# vm_mini_exp5.net
KiCad netlist of a schematic drawn in EAGLE
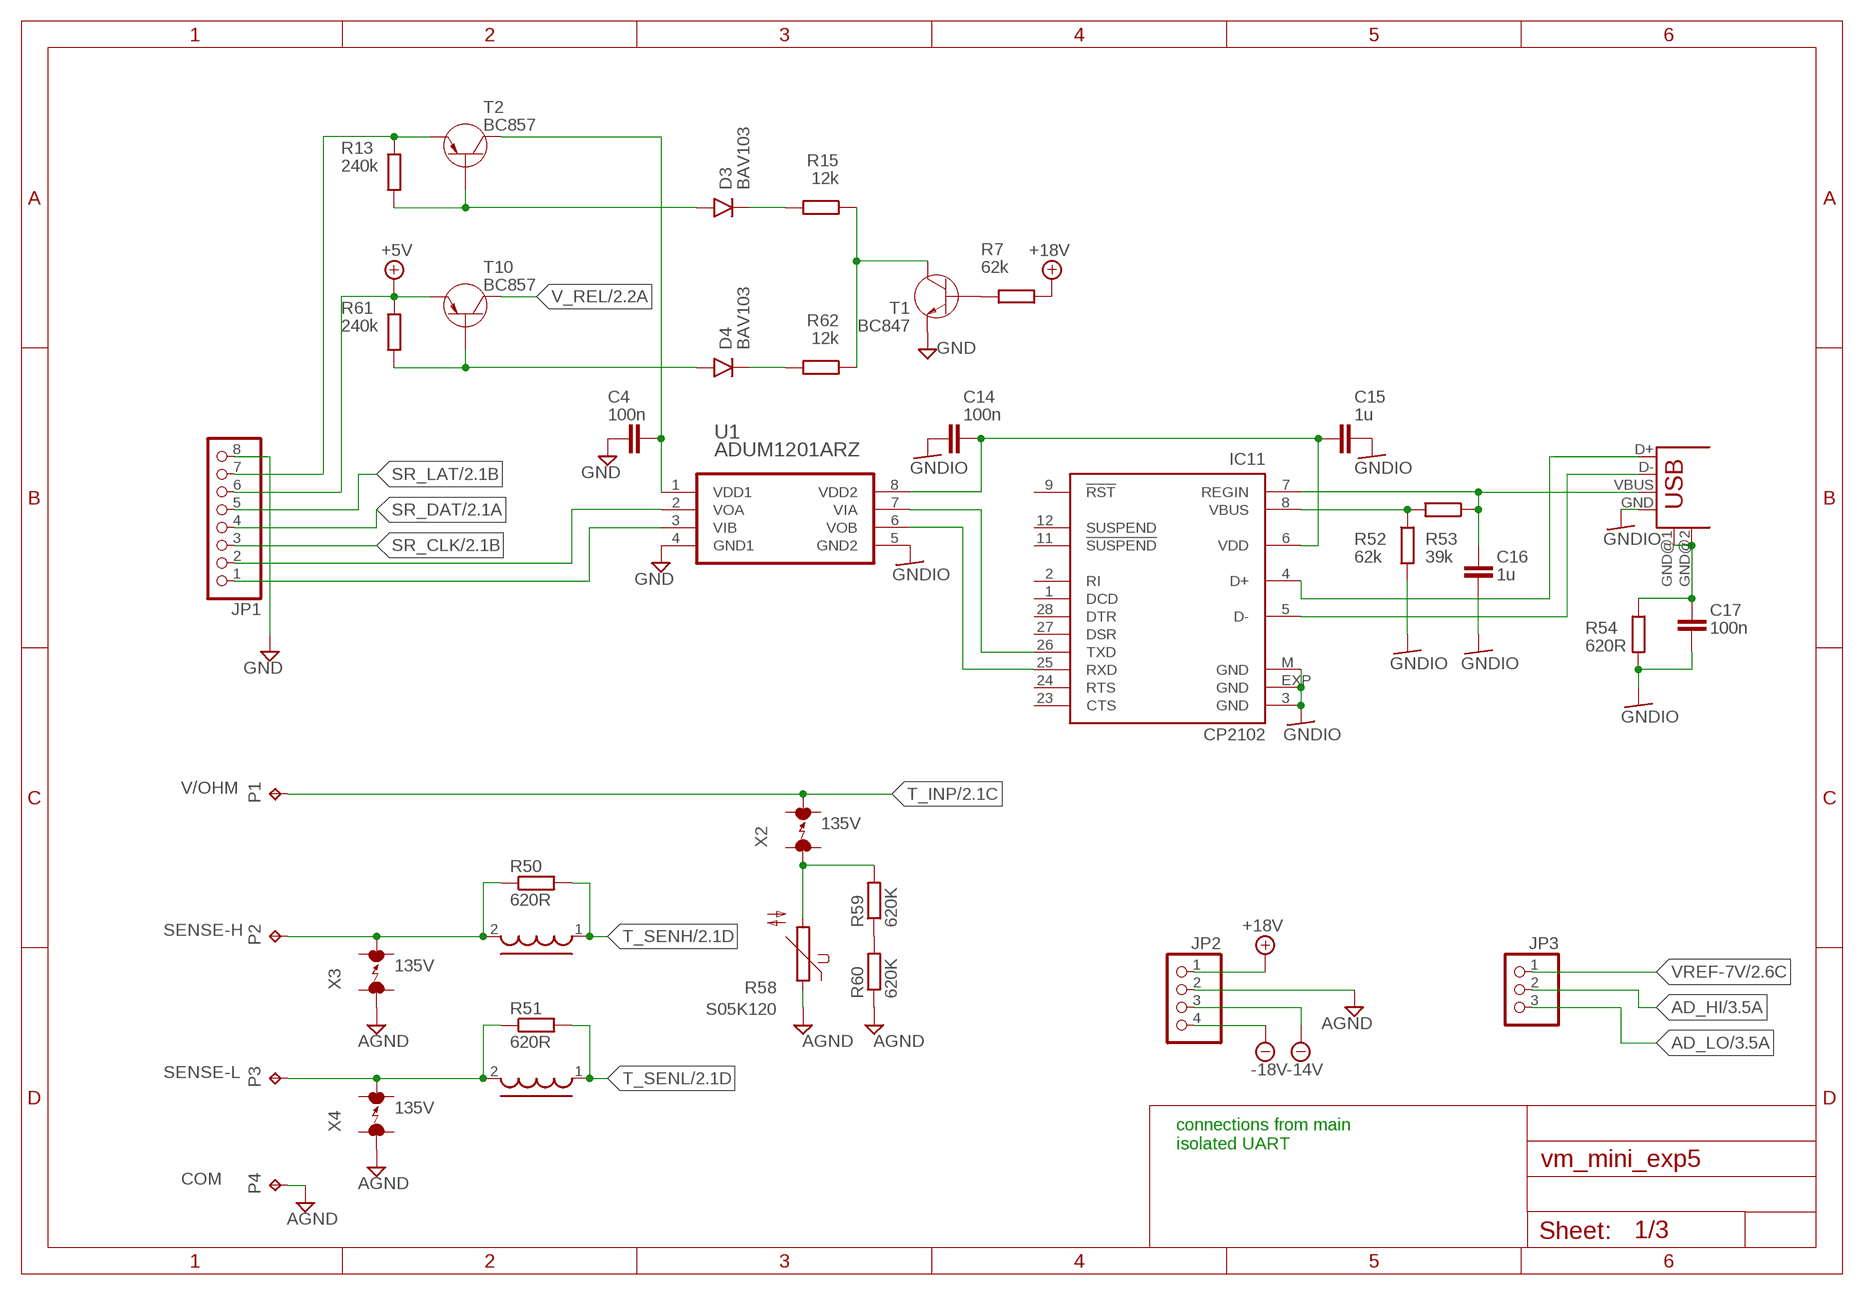
[diagram p0: schematic, sheet 1]
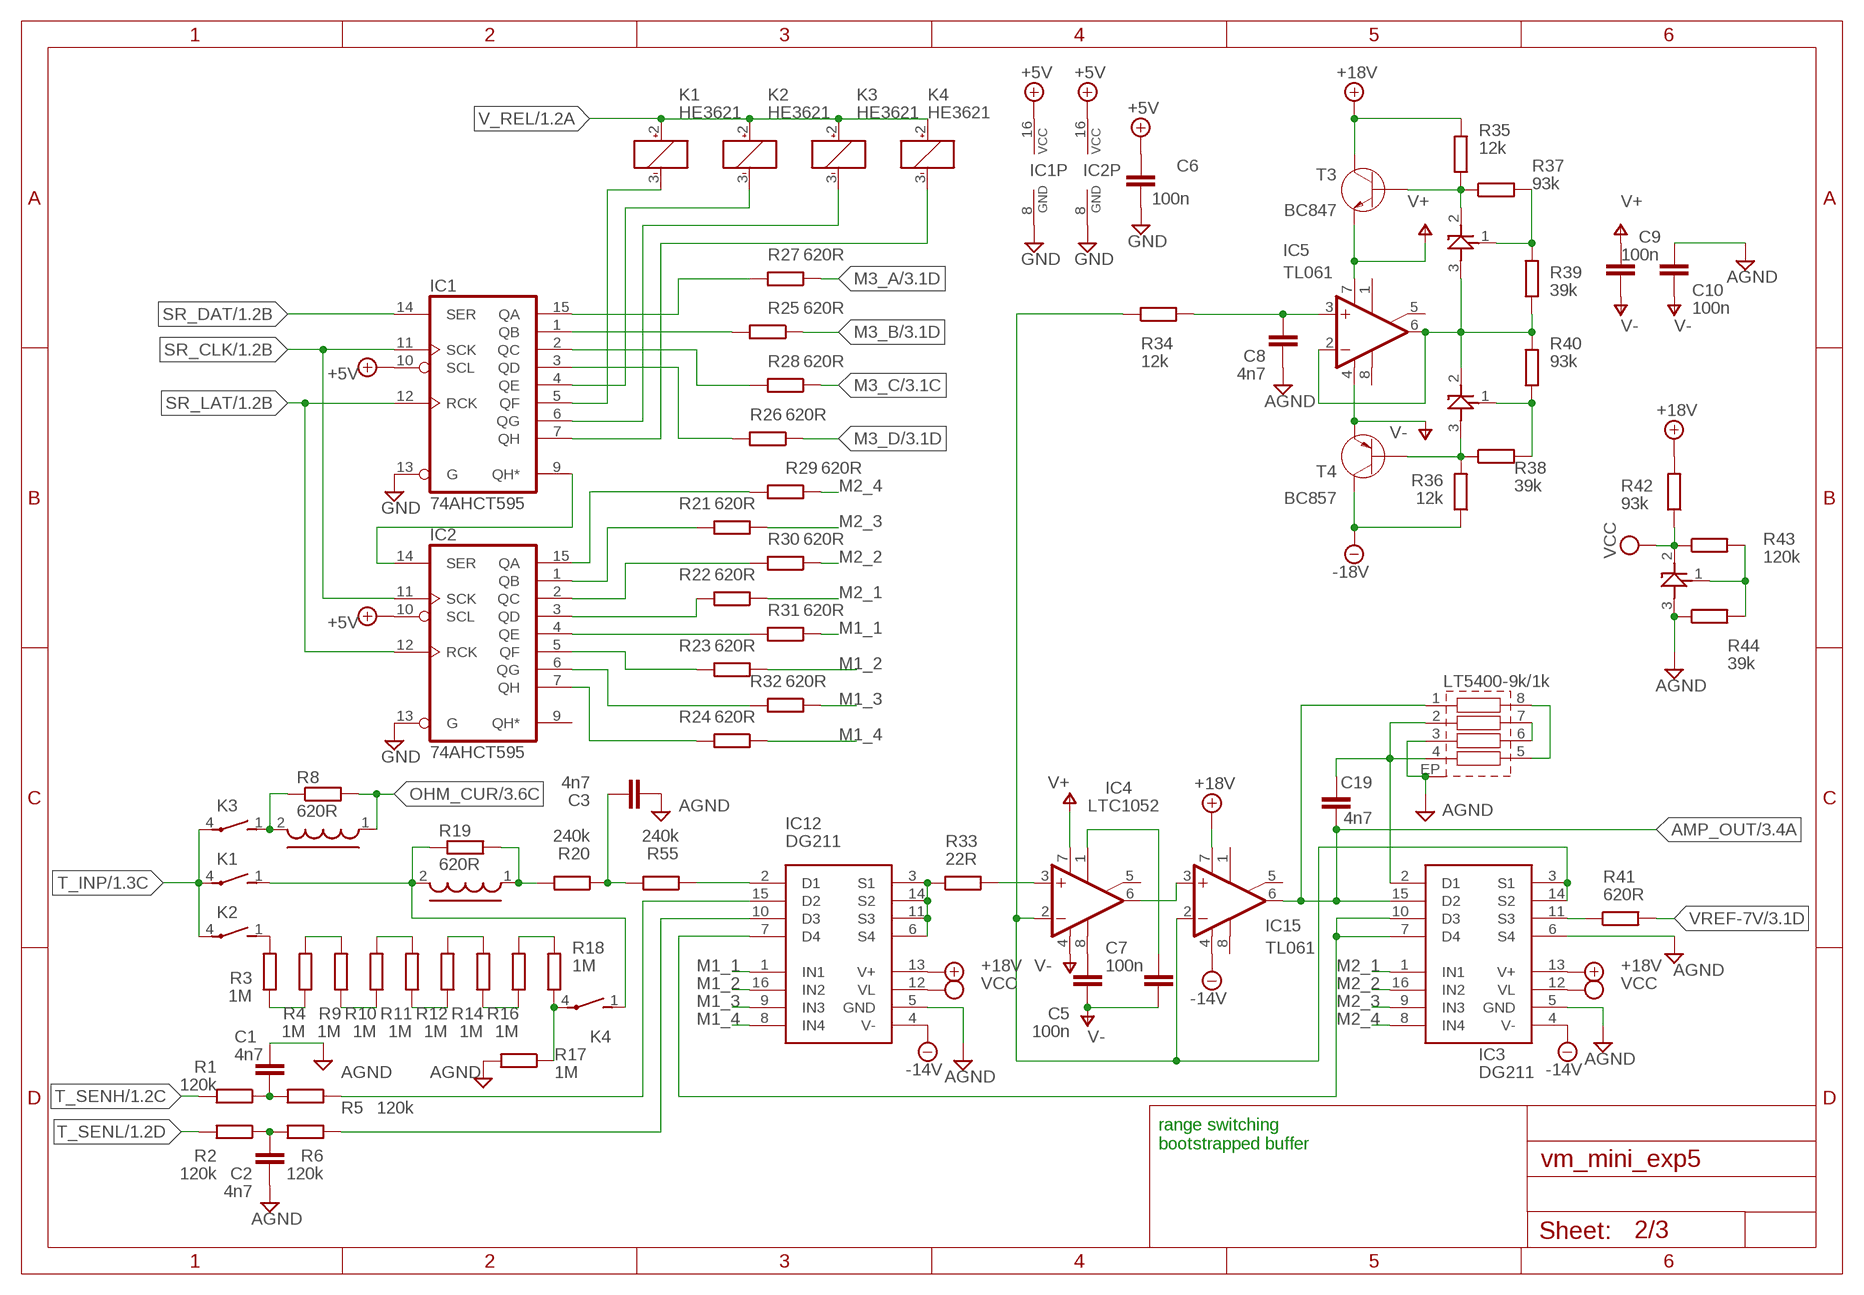
[diagram p1: schematic, sheet 2]
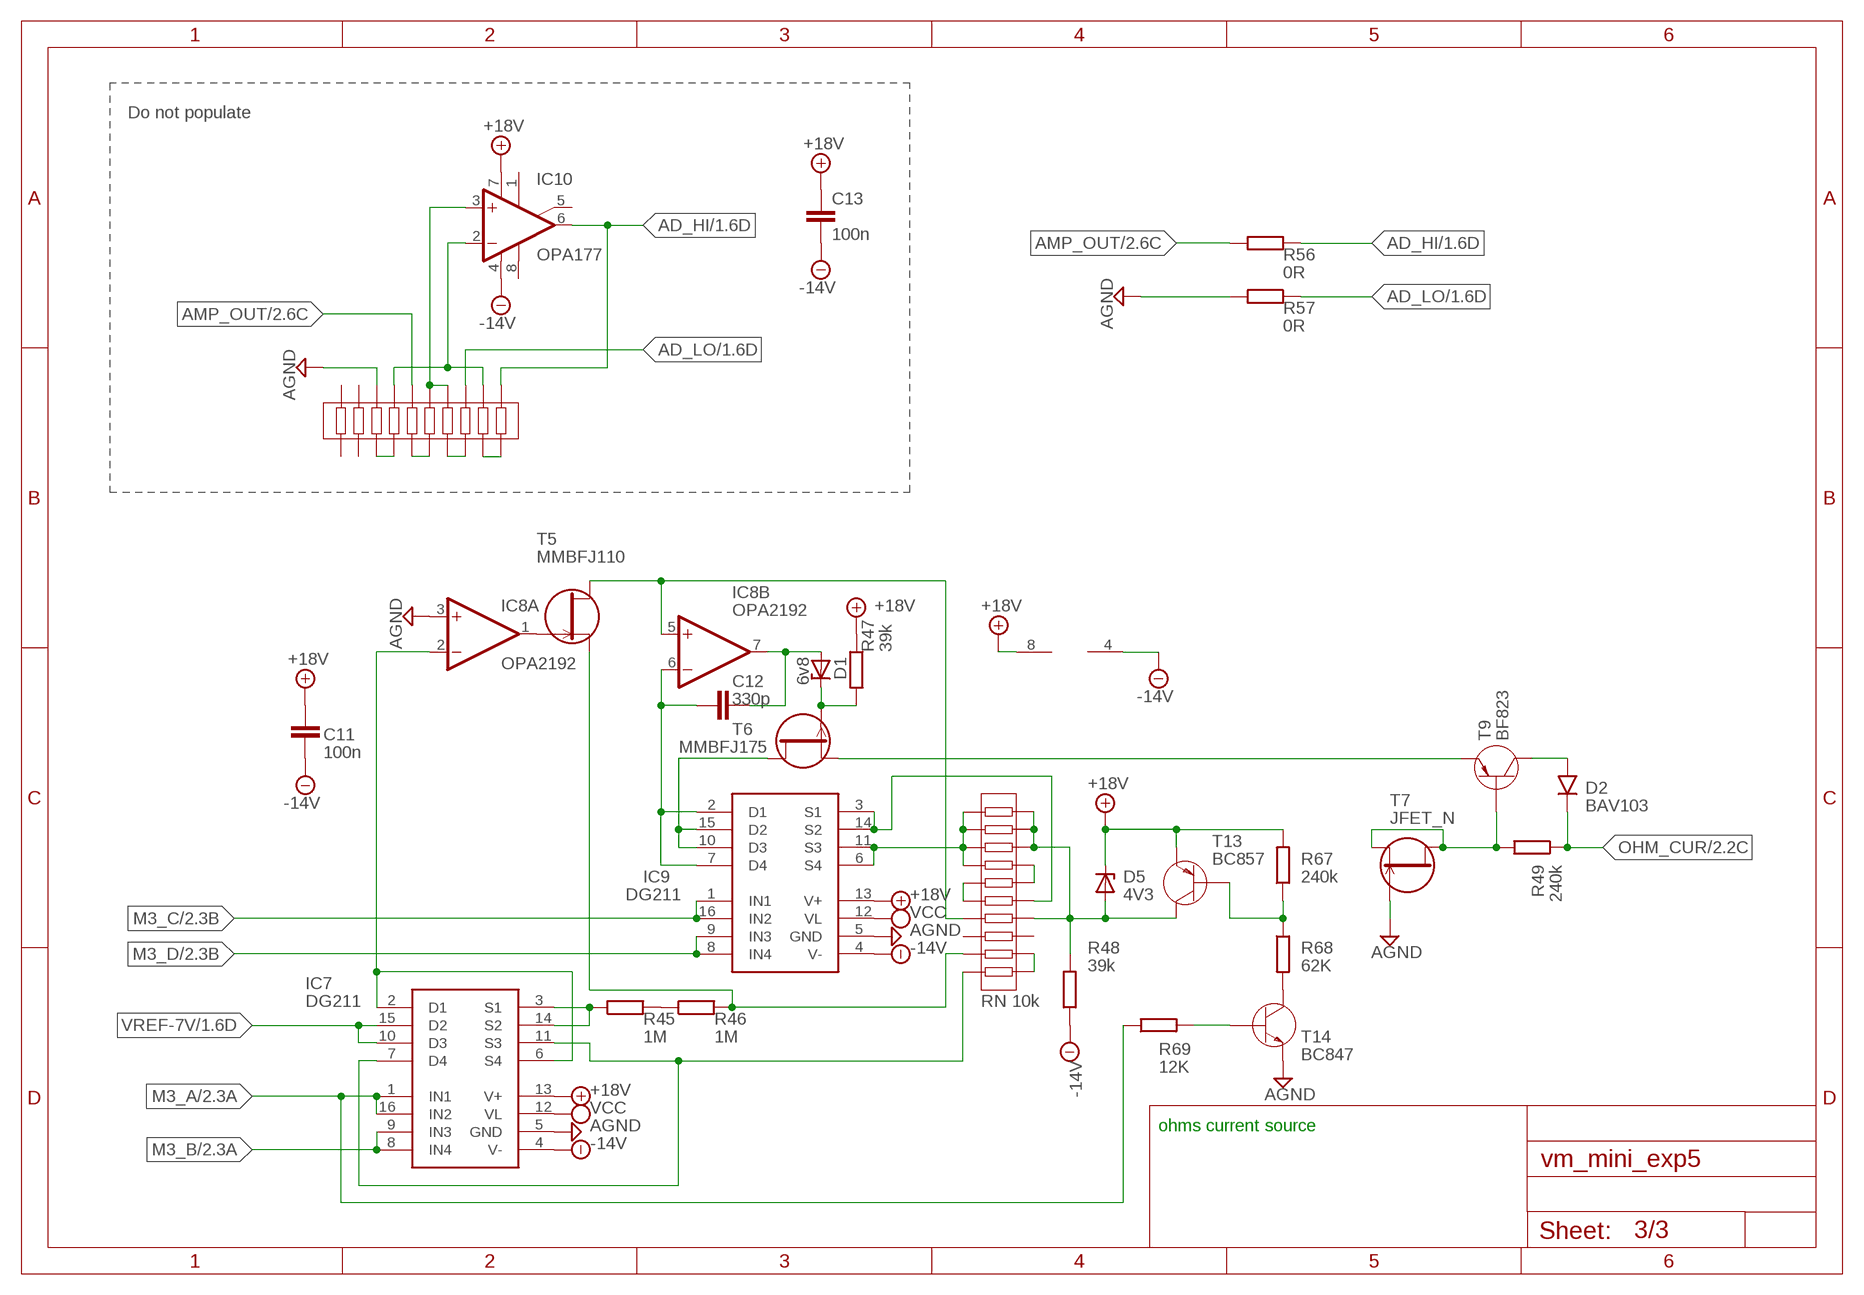
[diagram p2: schematic, sheet 3]

(export (version "E")
  (design (tool "Eeschema 10.0.6"))
  (components
    (comp (ref "C1")
      (value "4n7")
      (footprint "eagle-import:C050-025X075")
      (libsource (lib "eagle-import") (part "C-EU050-025X075"))
    )
    (comp (ref "C2")
      (value "4n7")
      (footprint "eagle-import:C050-025X075")
      (libsource (lib "eagle-import") (part "C-EU050-025X075"))
    )
    (comp (ref "C3")
      (value "4n7")
      (footprint "eagle-import:C050-025X075")
      (libsource (lib "eagle-import") (part "C-EU050-025X075"))
    )
    (comp (ref "C5")
      (value "100n")
      (footprint "eagle-import:C050-045X075")
      (libsource (lib "eagle-import") (part "C-EU050-045X075"))
    )
    (comp (ref "C6")
      (value "100n")
      (footprint "eagle-import:R0805")
      (libsource (lib "eagle-import") (part "C_0806"))
    )
    (comp (ref "C7")
      (value "100n")
      (footprint "eagle-import:C050-045X075")
      (libsource (lib "eagle-import") (part "C-EU050-045X075"))
    )
    (comp (ref "C8")
      (value "4n7")
      (footprint "eagle-import:C050-025X075")
      (libsource (lib "eagle-import") (part "C-EU050-025X075"))
    )
    (comp (ref "C9")
      (value "100n")
      (footprint "eagle-import:R0805")
      (libsource (lib "eagle-import") (part "C_0806"))
    )
    (comp (ref "C10")
      (value "100n")
      (footprint "eagle-import:R0805")
      (libsource (lib "eagle-import") (part "C_0806"))
    )
    (comp (ref "C19")
      (value "4n7")
      (footprint "eagle-import:C050-025X075")
      (libsource (lib "eagle-import") (part "C-EU050-025X075"))
    )
    (comp (ref "IC1")
      (value "74AHCT595")
      (footprint "eagle-import:SO16")
      (libsource (lib "eagle-import") (part "74595DHCT"))
    )
    (comp (ref "IC2")
      (value "74AHCT595")
      (footprint "eagle-import:SO16")
      (libsource (lib "eagle-import") (part "74595DHCT"))
    )
    (comp (ref "IC3")
      (value "DG211")
      (footprint "eagle-import:SO-16")
      (libsource (lib "eagle-import") (part "DG211"))
    )
    (comp (ref "IC4")
      (value "LTC1052")
      (footprint "eagle-import:DIL08")
      (libsource (lib "eagle-import") (part "TL071P"))
    )
    (comp (ref "IC5")
      (value "TL061")
      (footprint "eagle-import:SO08")
      (libsource (lib "eagle-import") (part "TL071D"))
    )
    (comp (ref "IC6")
      (value "TL431_SOT23")
      (footprint "eagle-import:SOT23")
      (libsource (lib "eagle-import") (part "TL431_SOT23"))
    )
    (comp (ref "IC12")
      (value "DG211")
      (footprint "eagle-import:SO-16")
      (libsource (lib "eagle-import") (part "DG211"))
    )
    (comp (ref "IC13")
      (value "TL431_SOT23")
      (footprint "eagle-import:SOT23")
      (libsource (lib "eagle-import") (part "TL431_SOT23"))
    )
    (comp (ref "IC14")
      (value "TL431_SOT23")
      (footprint "eagle-import:SOT23")
      (libsource (lib "eagle-import") (part "TL431_SOT23"))
    )
    (comp (ref "IC15")
      (value "TL061")
      (footprint "eagle-import:SO08")
      (libsource (lib "eagle-import") (part "TL071D"))
    )
    (comp (ref "K1")
      (value "HE3621")
      (footprint "eagle-import:HE3621")
      (libsource (lib "eagle-import") (part "HE3621"))
    )
    (comp (ref "K2")
      (value "HE3621")
      (footprint "eagle-import:HE3621")
      (libsource (lib "eagle-import") (part "HE3621"))
    )
    (comp (ref "K3")
      (value "HE3621")
      (footprint "eagle-import:HE3621")
      (libsource (lib "eagle-import") (part "HE3621"))
    )
    (comp (ref "K4")
      (value "HE3621")
      (footprint "eagle-import:HE3621")
      (libsource (lib "eagle-import") (part "HE3621"))
    )
    (comp (ref "R1")
      (value "120k")
      (footprint "eagle-import:R_MINIMELF")
      (libsource (lib "eagle-import") (part "RMMELF"))
    )
    (comp (ref "R2")
      (value "120k")
      (footprint "eagle-import:R_MINIMELF")
      (libsource (lib "eagle-import") (part "RMMELF"))
    )
    (comp (ref "R3")
      (value "1M")
      (footprint "eagle-import:R_MINIMELF")
      (libsource (lib "eagle-import") (part "RMMELF"))
    )
    (comp (ref "R4")
      (value "1M")
      (footprint "eagle-import:R_MINIMELF")
      (libsource (lib "eagle-import") (part "RMMELF"))
    )
    (comp (ref "R5")
      (value "120k")
      (footprint "eagle-import:R_MINIMELF")
      (libsource (lib "eagle-import") (part "RMMELF"))
    )
    (comp (ref "R6")
      (value "120k")
      (footprint "eagle-import:R_MINIMELF")
      (libsource (lib "eagle-import") (part "RMMELF"))
    )
    (comp (ref "R8")
      (value "620R")
      (footprint "eagle-import:R_MINIMELF")
      (libsource (lib "eagle-import") (part "RMMELF"))
    )
    (comp (ref "R9")
      (value "1M")
      (footprint "eagle-import:R_MINIMELF")
      (libsource (lib "eagle-import") (part "RMMELF"))
    )
    (comp (ref "R10")
      (value "1M")
      (footprint "eagle-import:R_MINIMELF")
      (libsource (lib "eagle-import") (part "RMMELF"))
    )
    (comp (ref "R11")
      (value "1M")
      (footprint "eagle-import:R_MINIMELF")
      (libsource (lib "eagle-import") (part "RMMELF"))
    )
    (comp (ref "R12")
      (value "1M")
      (footprint "eagle-import:R_MINIMELF")
      (libsource (lib "eagle-import") (part "RMMELF"))
    )
    (comp (ref "R14")
      (value "1M")
      (footprint "eagle-import:R_MINIMELF")
      (libsource (lib "eagle-import") (part "RMMELF"))
    )
    (comp (ref "R16")
      (value "1M")
      (footprint "eagle-import:R_MINIMELF")
      (libsource (lib "eagle-import") (part "RMMELF"))
    )
    (comp (ref "R17")
      (value "1M")
      (footprint "eagle-import:R_MINIMELF")
      (libsource (lib "eagle-import") (part "RMMELF"))
    )
    (comp (ref "R18")
      (value "1M")
      (footprint "eagle-import:R_MINIMELF")
      (libsource (lib "eagle-import") (part "RMMELF"))
    )
    (comp (ref "R19")
      (value "620R")
      (footprint "eagle-import:R_MINIMELF")
      (libsource (lib "eagle-import") (part "RMMELF"))
    )
    (comp (ref "R20")
      (value "240k")
      (footprint "eagle-import:R_MINIMELF")
      (libsource (lib "eagle-import") (part "RMMELF"))
    )
    (comp (ref "R21")
      (value "620R")
      (footprint "eagle-import:R_MINIMELF")
      (libsource (lib "eagle-import") (part "RMMELF"))
    )
    (comp (ref "R22")
      (value "620R")
      (footprint "eagle-import:R_MINIMELF")
      (libsource (lib "eagle-import") (part "RMMELF"))
    )
    (comp (ref "R23")
      (value "620R")
      (footprint "eagle-import:R_MINIMELF")
      (libsource (lib "eagle-import") (part "RMMELF"))
    )
    (comp (ref "R24")
      (value "620R")
      (footprint "eagle-import:R_MINIMELF")
      (libsource (lib "eagle-import") (part "RMMELF"))
    )
    (comp (ref "R25")
      (value "620R")
      (footprint "eagle-import:R_MINIMELF")
      (libsource (lib "eagle-import") (part "RMMELF"))
    )
    (comp (ref "R26")
      (value "620R")
      (footprint "eagle-import:R_MINIMELF")
      (libsource (lib "eagle-import") (part "RMMELF"))
    )
    (comp (ref "R27")
      (value "620R")
      (footprint "eagle-import:R_MINIMELF")
      (libsource (lib "eagle-import") (part "RMMELF"))
    )
    (comp (ref "R28")
      (value "620R")
      (footprint "eagle-import:R_MINIMELF")
      (libsource (lib "eagle-import") (part "RMMELF"))
    )
    (comp (ref "R29")
      (value "620R")
      (footprint "eagle-import:R_MINIMELF")
      (libsource (lib "eagle-import") (part "RMMELF"))
    )
    (comp (ref "R30")
      (value "620R")
      (footprint "eagle-import:R_MINIMELF")
      (libsource (lib "eagle-import") (part "RMMELF"))
    )
    (comp (ref "R31")
      (value "620R")
      (footprint "eagle-import:R_MINIMELF")
      (libsource (lib "eagle-import") (part "RMMELF"))
    )
    (comp (ref "R32")
      (value "620R")
      (footprint "eagle-import:R_MINIMELF")
      (libsource (lib "eagle-import") (part "RMMELF"))
    )
    (comp (ref "R33")
      (value "22R")
      (footprint "eagle-import:R_MINIMELF")
      (libsource (lib "eagle-import") (part "RMMELF"))
    )
    (comp (ref "R34")
      (value "12k")
      (footprint "eagle-import:R_MINIMELF")
      (libsource (lib "eagle-import") (part "RMMELF"))
    )
    (comp (ref "R35")
      (value "12k")
      (footprint "eagle-import:R_MINIMELF")
      (libsource (lib "eagle-import") (part "RMMELF"))
    )
    (comp (ref "R36")
      (value "12k")
      (footprint "eagle-import:R_MINIMELF")
      (libsource (lib "eagle-import") (part "RMMELF"))
    )
    (comp (ref "R37")
      (value "93k")
      (footprint "eagle-import:R_MINIMELF")
      (libsource (lib "eagle-import") (part "RMMELF"))
    )
    (comp (ref "R38")
      (value "39k")
      (footprint "eagle-import:R_MINIMELF")
      (libsource (lib "eagle-import") (part "RMMELF"))
    )
    (comp (ref "R39")
      (value "39k")
      (footprint "eagle-import:R_MINIMELF")
      (libsource (lib "eagle-import") (part "RMMELF"))
    )
    (comp (ref "R40")
      (value "93k")
      (footprint "eagle-import:R_MINIMELF")
      (libsource (lib "eagle-import") (part "RMMELF"))
    )
    (comp (ref "R41")
      (value "620R")
      (footprint "eagle-import:R_MINIMELF")
      (libsource (lib "eagle-import") (part "RMMELF"))
    )
    (comp (ref "R42")
      (value "93k")
      (footprint "eagle-import:R_MINIMELF")
      (libsource (lib "eagle-import") (part "RMMELF"))
    )
    (comp (ref "R43")
      (value "120k")
      (footprint "eagle-import:R_MINIMELF")
      (libsource (lib "eagle-import") (part "RMMELF"))
    )
    (comp (ref "R44")
      (value "39k")
      (footprint "eagle-import:R_MINIMELF")
      (libsource (lib "eagle-import") (part "RMMELF"))
    )
    (comp (ref "R55")
      (value "240k")
      (footprint "eagle-import:R_MINIMELF")
      (libsource (lib "eagle-import") (part "RMMELF"))
    )
    (comp (ref "RN3")
      (value "LT5400")
      (footprint "eagle-import:MSOP8-EP")
      (libsource (lib "eagle-import") (part "LT5400"))
    )
    (comp (ref "T3")
      (value "BC847")
      (footprint "eagle-import:SOT23")
      (libsource (lib "eagle-import") (part "BC847"))
    )
    (comp (ref "T4")
      (value "BC857")
      (footprint "eagle-import:SOT23")
      (libsource (lib "eagle-import") (part "BC857"))
    )
    (comp (ref "U$1")
      (value "INDUCTOR_GEN1210")
      (footprint "eagle-import:1210")
      (libsource (lib "eagle-import") (part "INDUCTOR_GEN1210"))
    )
    (comp (ref "U$2")
      (value "INDUCTOR_GEN1210")
      (footprint "eagle-import:1210")
      (libsource (lib "eagle-import") (part "INDUCTOR_GEN1210"))
    )
    (comp (ref "C11")
      (value "100n")
      (footprint "eagle-import:R0805")
      (libsource (lib "eagle-import") (part "C_0806"))
    )
    (comp (ref "C12")
      (value "330p")
      (footprint "eagle-import:R_MINIMELF")
      (libsource (lib "eagle-import") (part "CMM"))
    )
    (comp (ref "C13")
      (value "100n")
      (footprint "eagle-import:R0805")
      (libsource (lib "eagle-import") (part "C_0806"))
    )
    (comp (ref "D1")
      (value "6v8")
      (footprint "eagle-import:SOD80C")
      (libsource (lib "eagle-import") (part "ZENER-DIODESOD80C"))
    )
    (comp (ref "D2")
      (value "BAV103")
      (footprint "eagle-import:SOD-80")
      (libsource (lib "eagle-import") (part "1N4148SOD"))
    )
    (comp (ref "D5")
      (value "4V3")
      (footprint "eagle-import:SOD80C")
      (libsource (lib "eagle-import") (part "ZENER-DIODESOD80C"))
    )
    (comp (ref "IC7")
      (value "DG211")
      (footprint "eagle-import:SO-16")
      (libsource (lib "eagle-import") (part "DG211"))
    )
    (comp (ref "IC8")
      (value "OPA2192")
      (footprint "eagle-import:SO08")
      (libsource (lib "eagle-import") (part "TL072D"))
    )
    (comp (ref "IC9")
      (value "DG211")
      (footprint "eagle-import:SO-16")
      (libsource (lib "eagle-import") (part "DG211"))
    )
    (comp (ref "IC10")
      (value "OPA177")
      (footprint "eagle-import:SO08")
      (libsource (lib "eagle-import") (part "linear_TL071D"))
    )
    (comp (ref "R45")
      (value "1M")
      (footprint "eagle-import:R_MINIMELF")
      (libsource (lib "eagle-import") (part "RMMELF"))
    )
    (comp (ref "R46")
      (value "1M")
      (footprint "eagle-import:R_MINIMELF")
      (libsource (lib "eagle-import") (part "RMMELF"))
    )
    (comp (ref "R47")
      (value "39k")
      (footprint "eagle-import:R_MINIMELF")
      (libsource (lib "eagle-import") (part "RMMELF"))
    )
    (comp (ref "R48")
      (value "39k")
      (footprint "eagle-import:R_MINIMELF")
      (libsource (lib "eagle-import") (part "RMMELF"))
    )
    (comp (ref "R49")
      (value "240k")
      (footprint "eagle-import:R_MINIMELF")
      (libsource (lib "eagle-import") (part "RMMELF"))
    )
    (comp (ref "R56")
      (value "0R")
      (footprint "eagle-import:R_MINIMELF")
      (libsource (lib "eagle-import") (part "RMMELF"))
    )
    (comp (ref "R57")
      (value "0R")
      (footprint "eagle-import:R_MINIMELF")
      (libsource (lib "eagle-import") (part "RMMELF"))
    )
    (comp (ref "R67")
      (value "240k")
      (footprint "eagle-import:R_MINIMELF")
      (libsource (lib "eagle-import") (part "RMMELF"))
    )
    (comp (ref "R68")
      (value "62K")
      (footprint "eagle-import:R_MINIMELF")
      (libsource (lib "eagle-import") (part "RMMELF"))
    )
    (comp (ref "R69")
      (value "12K")
      (footprint "eagle-import:R_MINIMELF")
      (libsource (lib "eagle-import") (part "RMMELF"))
    )
    (comp (ref "RN1")
      (value "OSOP20")
      (footprint "eagle-import:OSOP20")
      (libsource (lib "eagle-import") (part "OSOP20"))
    )
    (comp (ref "RN2")
      (value "OSOP20")
      (footprint "eagle-import:OSOP20")
      (libsource (lib "eagle-import") (part "OSOP20"))
    )
    (comp (ref "T5")
      (value "MMBFJ110")
      (footprint "eagle-import:SOT23")
      (libsource (lib "eagle-import") (part "JFET_N"))
    )
    (comp (ref "T6")
      (value "MMBFJ175")
      (footprint "eagle-import:SOT23")
      (libsource (lib "eagle-import") (part "JFET_P"))
    )
    (comp (ref "T7")
      (value "JFET_N")
      (footprint "eagle-import:SOT23")
      (libsource (lib "eagle-import") (part "JFET_N"))
    )
    (comp (ref "T9")
      (value "BF823")
      (footprint "eagle-import:SOT23")
      (libsource (lib "eagle-import") (part "BC857"))
    )
    (comp (ref "T13")
      (value "BC857")
      (footprint "eagle-import:SOT23")
      (libsource (lib "eagle-import") (part "BC857"))
    )
    (comp (ref "T14")
      (value "BC847")
      (footprint "eagle-import:SOT23")
      (libsource (lib "eagle-import") (part "BC847"))
    )
    (comp (ref "C4")
      (value "100n")
      (footprint "eagle-import:R0805")
      (libsource (lib "eagle-import") (part "C_0806"))
    )
    (comp (ref "C14")
      (value "100n")
      (footprint "eagle-import:R0805")
      (libsource (lib "eagle-import") (part "C_0806"))
    )
    (comp (ref "C15")
      (value "1u")
      (footprint "eagle-import:R0805")
      (libsource (lib "eagle-import") (part "C_0806"))
    )
    (comp (ref "C16")
      (value "1u")
      (footprint "eagle-import:R0805")
      (libsource (lib "eagle-import") (part "C_0806"))
    )
    (comp (ref "C17")
      (value "100n")
      (footprint "eagle-import:R0805")
      (libsource (lib "eagle-import") (part "C_0806"))
    )
    (comp (ref "D3")
      (value "BAV103")
      (footprint "eagle-import:SOD-80")
      (libsource (lib "eagle-import") (part "1N4148SOD"))
    )
    (comp (ref "D4")
      (value "BAV103")
      (footprint "eagle-import:SOD-80")
      (libsource (lib "eagle-import") (part "1N4148SOD"))
    )
    (comp (ref "IC11")
      (value "CP2102")
      (footprint "eagle-import:MLP28")
      (fields (field (name "MF") "FARNELL") (field (name "MPN") "CP2102-GM"))
      (libsource (lib "eagle-import") (part "CP2102"))
    )
    (comp (ref "JP1")
      (value "PINHD-1X08_2.54")
      (footprint "eagle-import:1X08")
      (libsource (lib "eagle-import") (part "PINHD-1X08_2.54"))
    )
    (comp (ref "JP2")
      (value "PINHD-1X04_2.54")
      (footprint "eagle-import:1X04")
      (libsource (lib "eagle-import") (part "PINHD-1X04_2.54"))
    )
    (comp (ref "JP3")
      (value "PINHD-1X03_2.54")
      (footprint "eagle-import:1X03")
      (libsource (lib "eagle-import") (part "PINHD-1X03_2.54"))
    )
    (comp (ref "P1")
      (value "TPPAD1-17")
      (footprint "eagle-import:P1-17")
      (libsource (lib "eagle-import") (part "TPPAD1-17"))
    )
    (comp (ref "P2")
      (value "TPPAD1-17")
      (footprint "eagle-import:P1-17")
      (libsource (lib "eagle-import") (part "TPPAD1-17"))
    )
    (comp (ref "P3")
      (value "TPPAD1-17")
      (footprint "eagle-import:P1-17")
      (libsource (lib "eagle-import") (part "TPPAD1-17"))
    )
    (comp (ref "P4")
      (value "TPPAD1-17")
      (footprint "eagle-import:P1-17")
      (libsource (lib "eagle-import") (part "TPPAD1-17"))
    )
    (comp (ref "R7")
      (value "62k")
      (footprint "eagle-import:R_MINIMELF")
      (libsource (lib "eagle-import") (part "RMMELF"))
    )
    (comp (ref "R13")
      (value "240k")
      (footprint "eagle-import:R_MINIMELF")
      (libsource (lib "eagle-import") (part "RMMELF"))
    )
    (comp (ref "R15")
      (value "12k")
      (footprint "eagle-import:R_MINIMELF")
      (libsource (lib "eagle-import") (part "RMMELF"))
    )
    (comp (ref "R50")
      (value "620R")
      (footprint "eagle-import:R_MINIMELF")
      (libsource (lib "eagle-import") (part "RMMELF"))
    )
    (comp (ref "R51")
      (value "620R")
      (footprint "eagle-import:R_MINIMELF")
      (libsource (lib "eagle-import") (part "RMMELF"))
    )
    (comp (ref "R52")
      (value "62k")
      (footprint "eagle-import:R_MINIMELF")
      (libsource (lib "eagle-import") (part "RMMELF"))
    )
    (comp (ref "R53")
      (value "39k")
      (footprint "eagle-import:R_MINIMELF")
      (libsource (lib "eagle-import") (part "RMMELF"))
    )
    (comp (ref "R54")
      (value "620R")
      (footprint "eagle-import:R_MINIMELF")
      (libsource (lib "eagle-import") (part "RMMELF"))
    )
    (comp (ref "R58")
      (value "S05K120")
      (footprint "eagle-import:S05K175")
      (libsource (lib "eagle-import") (part "S05K175"))
    )
    (comp (ref "R59")
      (value "620K")
      (footprint "eagle-import:R_MINIMELF")
      (libsource (lib "eagle-import") (part "RMMELF"))
    )
    (comp (ref "R60")
      (value "620K")
      (footprint "eagle-import:R_MINIMELF")
      (libsource (lib "eagle-import") (part "RMMELF"))
    )
    (comp (ref "R61")
      (value "240k")
      (footprint "eagle-import:R_MINIMELF")
      (libsource (lib "eagle-import") (part "RMMELF"))
    )
    (comp (ref "R62")
      (value "12k")
      (footprint "eagle-import:R_MINIMELF")
      (libsource (lib "eagle-import") (part "RMMELF"))
    )
    (comp (ref "T1")
      (value "BC847")
      (footprint "eagle-import:SOT23")
      (libsource (lib "eagle-import") (part "BC847"))
    )
    (comp (ref "T2")
      (value "BC857")
      (footprint "eagle-import:SOT23")
      (libsource (lib "eagle-import") (part "BC857"))
    )
    (comp (ref "T10")
      (value "BC857")
      (footprint "eagle-import:SOT23")
      (libsource (lib "eagle-import") (part "BC857"))
    )
    (comp (ref "U$7")
      (value "INDUCTOR_GEN1210")
      (footprint "eagle-import:1210")
      (libsource (lib "eagle-import") (part "INDUCTOR_GEN1210"))
    )
    (comp (ref "U$8")
      (value "INDUCTOR_GEN1210")
      (footprint "eagle-import:1210")
      (libsource (lib "eagle-import") (part "INDUCTOR_GEN1210"))
    )
    (comp (ref "U1")
      (value "ADUM1201ARZ")
      (footprint "eagle-import:SOIC127P600X175-8N")
      (libsource (lib "eagle-import") (part "ADUM1201ARZ"))
    )
    (comp (ref "USB1")
      (value "USB-B-H")
      (footprint "eagle-import:USB-B-H")
      (libsource (lib "eagle-import") (part "USB-B-H"))
    )
    (comp (ref "X2")
      (value "135V")
      (footprint "eagle-import:EPCOS_N81")
      (libsource (lib "eagle-import") (part "ARRESTER"))
    )
    (comp (ref "X3")
      (value "135V")
      (footprint "eagle-import:EPCOS_N81")
      (libsource (lib "eagle-import") (part "ARRESTER"))
    )
    (comp (ref "X4")
      (value "135V")
      (footprint "eagle-import:EPCOS_N81")
      (libsource (lib "eagle-import") (part "ARRESTER"))
    )
  )
  (nets
    (net (code "1") (name "+5V") (class "Default")
      (node (ref "C6") (pin "1") (pinfunction "1_1") (pintype "passive"))
      (node (ref "IC1") (pin "10") (pinfunction "SCL_10") (pintype "input"))
      (node (ref "IC1") (pin "16") (pinfunction "VCC_16") (pintype "power_in"))
      (node (ref "IC2") (pin "10") (pinfunction "SCL_10") (pintype "input"))
      (node (ref "IC2") (pin "16") (pinfunction "VCC_16") (pintype "power_in"))
      (node (ref "JP1") (pin "6") (pinfunction "6_6") (pintype "passive"))
      (node (ref "R61") (pin "P$1") (pinfunction "1_P$1") (pintype "passive"))
      (node (ref "T10") (pin "2") (pinfunction "C_2") (pintype "passive"))
    )
    (net (code "2") (name "+18V") (class "Default")
      (node (ref "C11") (pin "1") (pinfunction "1_1") (pintype "passive"))
      (node (ref "C13") (pin "1") (pinfunction "1_1") (pintype "passive"))
      (node (ref "D5") (pin "C") (pinfunction "C_C") (pintype "passive"))
      (node (ref "IC10") (pin "7") (pinfunction "V+_7") (pintype "power_in"))
      (node (ref "IC12") (pin "13") (pinfunction "V+_13") (pintype "bidirectional"))
      (node (ref "IC15") (pin "7") (pinfunction "V+_7") (pintype "power_in"))
      (node (ref "IC3") (pin "13") (pinfunction "V+_13") (pintype "bidirectional"))
      (node (ref "IC7") (pin "13") (pinfunction "V+_13") (pintype "bidirectional"))
      (node (ref "IC8") (pin "8") (pinfunction "V+_8") (pintype "power_in"))
      (node (ref "IC9") (pin "13") (pinfunction "V+_13") (pintype "bidirectional"))
      (node (ref "JP2") (pin "1") (pinfunction "1_1") (pintype "passive"))
      (node (ref "R35") (pin "P$2") (pinfunction "2_P$2") (pintype "passive"))
      (node (ref "R42") (pin "P$2") (pinfunction "2_P$2") (pintype "passive"))
      (node (ref "R47") (pin "P$1") (pinfunction "1_P$1") (pintype "passive"))
      (node (ref "R67") (pin "P$2") (pinfunction "2_P$2") (pintype "passive"))
      (node (ref "R7") (pin "P$2") (pinfunction "2_P$2") (pintype "passive"))
      (node (ref "T13") (pin "2") (pinfunction "C_2") (pintype "passive"))
      (node (ref "T3") (pin "3") (pinfunction "C_3") (pintype "passive"))
    )
    (net (code "3") (name "-14V") (class "Default")
      (node (ref "C11") (pin "2") (pinfunction "2_2") (pintype "passive"))
      (node (ref "C13") (pin "2") (pinfunction "2_2") (pintype "passive"))
      (node (ref "IC10") (pin "4") (pinfunction "V-_4") (pintype "power_in"))
      (node (ref "IC12") (pin "4") (pinfunction "V-_4") (pintype "bidirectional"))
      (node (ref "IC15") (pin "4") (pinfunction "V-_4") (pintype "power_in"))
      (node (ref "IC3") (pin "4") (pinfunction "V-_4") (pintype "bidirectional"))
      (node (ref "IC7") (pin "4") (pinfunction "V-_4") (pintype "bidirectional"))
      (node (ref "IC8") (pin "4") (pinfunction "V-_4") (pintype "power_in"))
      (node (ref "IC9") (pin "4") (pinfunction "V-_4") (pintype "bidirectional"))
      (node (ref "JP2") (pin "3") (pinfunction "3_3") (pintype "passive"))
      (node (ref "R48") (pin "P$1") (pinfunction "1_P$1") (pintype "passive"))
    )
    (net (code "4") (name "-18V") (class "Default")
      (node (ref "JP2") (pin "4") (pinfunction "4_4") (pintype "passive"))
      (node (ref "R36") (pin "P$1") (pinfunction "1_P$1") (pintype "passive"))
      (node (ref "T4") (pin "3") (pinfunction "E_3") (pintype "passive"))
    )
    (net (code "5") (name "AD_HI") (class "Default")
      (node (ref "IC10") (pin "6") (pinfunction "OUT_6") (pintype "output"))
      (node (ref "JP3") (pin "2") (pinfunction "2_2") (pintype "passive"))
      (node (ref "R56") (pin "P$1") (pinfunction "1_P$1") (pintype "passive"))
      (node (ref "RN1") (pin "1") (pinfunction "1A_1") (pintype "bidirectional"))
    )
    (net (code "6") (name "AD_LO") (class "Default")
      (node (ref "JP3") (pin "3") (pinfunction "3_3") (pintype "passive"))
      (node (ref "R57") (pin "P$1") (pinfunction "1_P$1") (pintype "passive"))
      (node (ref "RN1") (pin "3") (pinfunction "3A_3") (pintype "bidirectional"))
    )
    (net (code "7") (name "AGND") (class "Default")
      (node (ref "C1") (pin "1") (pinfunction "1_1") (pintype "passive"))
      (node (ref "C10") (pin "1") (pinfunction "1_1") (pintype "passive"))
      (node (ref "C2") (pin "1") (pinfunction "1_1") (pintype "passive"))
      (node (ref "C3") (pin "1") (pinfunction "1_1") (pintype "passive"))
      (node (ref "C8") (pin "1") (pinfunction "1_1") (pintype "passive"))
      (node (ref "IC12") (pin "5") (pinfunction "GND_5") (pintype "bidirectional"))
      (node (ref "IC3") (pin "5") (pinfunction "GND_5") (pintype "bidirectional"))
      (node (ref "IC3") (pin "6") (pinfunction "S4_6") (pintype "bidirectional"))
      (node (ref "IC6") (pin "3") (pinfunction "A_3") (pintype "bidirectional"))
      (node (ref "IC7") (pin "5") (pinfunction "GND_5") (pintype "bidirectional"))
      (node (ref "IC8") (pin "3") (pinfunction "+IN_3") (pintype "input"))
      (node (ref "IC9") (pin "5") (pinfunction "GND_5") (pintype "bidirectional"))
      (node (ref "JP2") (pin "2") (pinfunction "2_2") (pintype "passive"))
      (node (ref "P4") (pin "TP") (pinfunction "TP_TP") (pintype "input"))
      (node (ref "R17") (pin "P$2") (pinfunction "2_P$2") (pintype "passive"))
      (node (ref "R44") (pin "P$1") (pinfunction "1_P$1") (pintype "passive"))
      (node (ref "R57") (pin "P$2") (pinfunction "2_P$2") (pintype "passive"))
      (node (ref "R58") (pin "1") (pinfunction "1_1") (pintype "passive"))
      (node (ref "R60") (pin "P$1") (pinfunction "1_P$1") (pintype "passive"))
      (node (ref "RN1") (pin "8") (pinfunction "8A_8") (pintype "bidirectional"))
      (node (ref "RN3") (pin "3") (pinfunction "R3A_3") (pintype "bidirectional"))
      (node (ref "RN3") (pin "EP") (pinfunction "SH_EP") (pintype "bidirectional"))
      (node (ref "T14") (pin "2") (pinfunction "E_2") (pintype "passive"))
      (node (ref "T7") (pin "3") (pinfunction "G_3") (pintype "bidirectional"))
      (node (ref "X3") (pin "1") (pinfunction "1_1") (pintype "passive"))
      (node (ref "X4") (pin "1") (pinfunction "1_1") (pintype "passive"))
    )
    (net (code "8") (name "AMP_OUT") (class "Default")
      (node (ref "C19") (pin "1") (pinfunction "1_1") (pintype "passive"))
      (node (ref "IC15") (pin "6") (pinfunction "OUT_6") (pintype "output"))
      (node (ref "IC3") (pin "15") (pinfunction "D2_15") (pintype "bidirectional"))
      (node (ref "R56") (pin "P$2") (pinfunction "2_P$2") (pintype "passive"))
      (node (ref "RN1") (pin "6") (pinfunction "6A_6") (pintype "bidirectional"))
      (node (ref "RN3") (pin "1") (pinfunction "R1A_1") (pintype "bidirectional"))
    )
    (net (code "9") (name "GND") (class "Default")
      (node (ref "C4") (pin "1") (pinfunction "1_1") (pintype "passive"))
      (node (ref "C6") (pin "2") (pinfunction "2_2") (pintype "passive"))
      (node (ref "IC1") (pin "13") (pinfunction "G_13") (pintype "input"))
      (node (ref "IC1") (pin "8") (pinfunction "GND_8") (pintype "power_in"))
      (node (ref "IC2") (pin "13") (pinfunction "G_13") (pintype "input"))
      (node (ref "IC2") (pin "8") (pinfunction "GND_8") (pintype "power_in"))
      (node (ref "JP1") (pin "8") (pinfunction "8_8") (pintype "passive"))
      (node (ref "T1") (pin "2") (pinfunction "E_2") (pintype "passive"))
      (node (ref "U1") (pin "4") (pinfunction "GND1_4") (pintype "passive"))
    )
    (net (code "10") (name "GNDIO") (class "Default")
      (node (ref "C14") (pin "1") (pinfunction "1_1") (pintype "passive"))
      (node (ref "C15") (pin "2") (pinfunction "2_2") (pintype "passive"))
      (node (ref "C16") (pin "1") (pinfunction "1_1") (pintype "passive"))
      (node (ref "C17") (pin "1") (pinfunction "1_1") (pintype "passive"))
      (node (ref "IC11") (pin "3") (pinfunction "GND_3") (pintype "power_in"))
      (node (ref "IC11") (pin "EXP") (pinfunction "GND_EXP") (pintype "power_in"))
      (node (ref "IC11") (pin "M") (pinfunction "GND_M") (pintype "power_in"))
      (node (ref "R52") (pin "P$2") (pinfunction "2_P$2") (pintype "passive"))
      (node (ref "R54") (pin "P$2") (pinfunction "2_P$2") (pintype "passive"))
      (node (ref "U1") (pin "5") (pinfunction "GND2_5") (pintype "passive"))
      (node (ref "USB1") (pin "GND") (pinfunction "GND_GND") (pintype "bidirectional"))
    )
    (net (code "11") (name "M1_1") (class "Default")
      (node (ref "IC12") (pin "1") (pinfunction "IN1_1") (pintype "bidirectional"))
      (node (ref "R31") (pin "P$1") (pinfunction "1_P$1") (pintype "passive"))
    )
    (net (code "12") (name "M1_2") (class "Default")
      (node (ref "IC12") (pin "16") (pinfunction "IN2_16") (pintype "bidirectional"))
      (node (ref "R23") (pin "P$1") (pinfunction "1_P$1") (pintype "passive"))
    )
    (net (code "13") (name "M1_3") (class "Default")
      (node (ref "IC12") (pin "9") (pinfunction "IN3_9") (pintype "bidirectional"))
      (node (ref "R32") (pin "P$1") (pinfunction "1_P$1") (pintype "passive"))
    )
    (net (code "14") (name "M1_4") (class "Default")
      (node (ref "IC12") (pin "8") (pinfunction "IN4_8") (pintype "bidirectional"))
      (node (ref "R24") (pin "P$1") (pinfunction "1_P$1") (pintype "passive"))
    )
    (net (code "15") (name "M2_1") (class "Default")
      (node (ref "IC3") (pin "1") (pinfunction "IN1_1") (pintype "bidirectional"))
      (node (ref "R22") (pin "P$1") (pinfunction "1_P$1") (pintype "passive"))
    )
    (net (code "16") (name "M2_2") (class "Default")
      (node (ref "IC3") (pin "16") (pinfunction "IN2_16") (pintype "bidirectional"))
      (node (ref "R30") (pin "P$1") (pinfunction "1_P$1") (pintype "passive"))
    )
    (net (code "17") (name "M2_3") (class "Default")
      (node (ref "IC3") (pin "9") (pinfunction "IN3_9") (pintype "bidirectional"))
      (node (ref "R21") (pin "P$1") (pinfunction "1_P$1") (pintype "passive"))
    )
    (net (code "18") (name "M2_4") (class "Default")
      (node (ref "IC3") (pin "8") (pinfunction "IN4_8") (pintype "bidirectional"))
      (node (ref "R29") (pin "P$1") (pinfunction "1_P$1") (pintype "passive"))
    )
    (net (code "19") (name "M3_A") (class "Default")
      (node (ref "IC7") (pin "1") (pinfunction "IN1_1") (pintype "bidirectional"))
      (node (ref "IC7") (pin "16") (pinfunction "IN2_16") (pintype "bidirectional"))
      (node (ref "R27") (pin "P$1") (pinfunction "1_P$1") (pintype "passive"))
      (node (ref "R69") (pin "P$1") (pinfunction "1_P$1") (pintype "passive"))
    )
    (net (code "20") (name "M3_B") (class "Default")
      (node (ref "IC7") (pin "8") (pinfunction "IN4_8") (pintype "bidirectional"))
      (node (ref "IC7") (pin "9") (pinfunction "IN3_9") (pintype "bidirectional"))
      (node (ref "R25") (pin "P$1") (pinfunction "1_P$1") (pintype "passive"))
    )
    (net (code "21") (name "M3_C") (class "Default")
      (node (ref "IC9") (pin "1") (pinfunction "IN1_1") (pintype "bidirectional"))
      (node (ref "IC9") (pin "16") (pinfunction "IN2_16") (pintype "bidirectional"))
      (node (ref "R28") (pin "P$1") (pinfunction "1_P$1") (pintype "passive"))
    )
    (net (code "22") (name "M3_D") (class "Default")
      (node (ref "IC9") (pin "8") (pinfunction "IN4_8") (pintype "bidirectional"))
      (node (ref "IC9") (pin "9") (pinfunction "IN3_9") (pintype "bidirectional"))
      (node (ref "R26") (pin "P$1") (pinfunction "1_P$1") (pintype "passive"))
    )
    (net (code "23") (name "Net-(C12-1)") (class "Default")
      (node (ref "C12") (pin "P$1") (pinfunction "1_P$1") (pintype "passive"))
      (node (ref "IC8") (pin "6") (pinfunction "-IN_6") (pintype "input"))
      (node (ref "IC9") (pin "2") (pinfunction "D1_2") (pintype "bidirectional"))
      (node (ref "IC9") (pin "7") (pinfunction "D4_7") (pintype "bidirectional"))
    )
    (net (code "24") (name "Net-(C12-2)") (class "Default")
      (node (ref "C12") (pin "P$2") (pinfunction "2_P$2") (pintype "passive"))
      (node (ref "D1") (pin "A") (pinfunction "A_A") (pintype "passive"))
      (node (ref "IC8") (pin "7") (pinfunction "OUT_7") (pintype "output"))
    )
    (net (code "25") (name "Net-(IC1A-QA)") (class "Default")
      (node (ref "IC1") (pin "15") (pinfunction "QA_15") (pintype "tri_state"))
      (node (ref "R27") (pin "P$2") (pinfunction "2_P$2") (pintype "passive"))
    )
    (net (code "26") (name "Net-(IC1A-QB)") (class "Default")
      (node (ref "IC1") (pin "1") (pinfunction "QB_1") (pintype "tri_state"))
      (node (ref "R25") (pin "P$2") (pinfunction "2_P$2") (pintype "passive"))
    )
    (net (code "27") (name "Net-(IC1A-QC)") (class "Default")
      (node (ref "IC1") (pin "2") (pinfunction "QC_2") (pintype "tri_state"))
      (node (ref "R28") (pin "P$2") (pinfunction "2_P$2") (pintype "passive"))
    )
    (net (code "28") (name "Net-(IC1A-QD)") (class "Default")
      (node (ref "IC1") (pin "3") (pinfunction "QD_3") (pintype "tri_state"))
      (node (ref "R26") (pin "P$2") (pinfunction "2_P$2") (pintype "passive"))
    )
    (net (code "29") (name "Net-(IC1A-QE)") (class "Default")
      (node (ref "IC1") (pin "4") (pinfunction "QE_4") (pintype "tri_state"))
      (node (ref "K2") (pin "3") (pinfunction "-_3") (pintype "passive"))
    )
    (net (code "30") (name "Net-(IC1A-QF)") (class "Default")
      (node (ref "IC1") (pin "5") (pinfunction "QF_5") (pintype "tri_state"))
      (node (ref "K1") (pin "3") (pinfunction "-_3") (pintype "passive"))
    )
    (net (code "31") (name "Net-(IC1A-QG)") (class "Default")
      (node (ref "IC1") (pin "6") (pinfunction "QG_6") (pintype "tri_state"))
      (node (ref "K3") (pin "3") (pinfunction "-_3") (pintype "passive"))
    )
    (net (code "32") (name "Net-(IC1A-QH)") (class "Default")
      (node (ref "IC1") (pin "7") (pinfunction "QH_7") (pintype "tri_state"))
      (node (ref "K4") (pin "3") (pinfunction "-_3") (pintype "passive"))
    )
    (net (code "33") (name "Net-(IC1A-QH*)") (class "Default")
      (node (ref "IC1") (pin "9") (pinfunction "QH*_9") (pintype "tri_state"))
      (node (ref "IC2") (pin "14") (pinfunction "SER_14") (pintype "input"))
    )
    (net (code "34") (name "Net-(IC2A-QA)") (class "Default")
      (node (ref "IC2") (pin "15") (pinfunction "QA_15") (pintype "tri_state"))
      (node (ref "R29") (pin "P$2") (pinfunction "2_P$2") (pintype "passive"))
    )
    (net (code "35") (name "Net-(IC2A-QB)") (class "Default")
      (node (ref "IC2") (pin "1") (pinfunction "QB_1") (pintype "tri_state"))
      (node (ref "R21") (pin "P$2") (pinfunction "2_P$2") (pintype "passive"))
    )
    (net (code "36") (name "Net-(IC2A-QC)") (class "Default")
      (node (ref "IC2") (pin "2") (pinfunction "QC_2") (pintype "tri_state"))
      (node (ref "R30") (pin "P$2") (pinfunction "2_P$2") (pintype "passive"))
    )
    (net (code "37") (name "Net-(IC2A-QD)") (class "Default")
      (node (ref "IC2") (pin "3") (pinfunction "QD_3") (pintype "tri_state"))
      (node (ref "R22") (pin "P$2") (pinfunction "2_P$2") (pintype "passive"))
    )
    (net (code "38") (name "Net-(IC2A-QE)") (class "Default")
      (node (ref "IC2") (pin "4") (pinfunction "QE_4") (pintype "tri_state"))
      (node (ref "R31") (pin "P$2") (pinfunction "2_P$2") (pintype "passive"))
    )
    (net (code "39") (name "Net-(IC2A-QF)") (class "Default")
      (node (ref "IC2") (pin "5") (pinfunction "QF_5") (pintype "tri_state"))
      (node (ref "R23") (pin "P$2") (pinfunction "2_P$2") (pintype "passive"))
    )
    (net (code "40") (name "Net-(IC2A-QG)") (class "Default")
      (node (ref "IC2") (pin "6") (pinfunction "QG_6") (pintype "tri_state"))
      (node (ref "R32") (pin "P$2") (pinfunction "2_P$2") (pintype "passive"))
    )
    (net (code "41") (name "Net-(IC2A-QH)") (class "Default")
      (node (ref "IC2") (pin "7") (pinfunction "QH_7") (pintype "tri_state"))
      (node (ref "R24") (pin "P$2") (pinfunction "2_P$2") (pintype "passive"))
    )
    (net (code "42") (name "Net-(IC3-D1)") (class "Default")
      (node (ref "C19") (pin "2") (pinfunction "2_2") (pintype "passive"))
      (node (ref "IC3") (pin "2") (pinfunction "D1_2") (pintype "bidirectional"))
      (node (ref "RN3") (pin "2") (pinfunction "R2A_2") (pintype "bidirectional"))
      (node (ref "RN3") (pin "4") (pinfunction "R4A_4") (pintype "bidirectional"))
    )
    (net (code "43") (name "Net-(IC3-S3)") (class "Default")
      (node (ref "IC3") (pin "11") (pinfunction "S3_11") (pintype "bidirectional"))
      (node (ref "R41") (pin "P$1") (pinfunction "1_P$1") (pintype "passive"))
    )
    (net (code "44") (name "Net-(IC4-+IN)") (class "Default")
      (node (ref "IC4") (pin "3") (pinfunction "+IN_3") (pintype "input"))
      (node (ref "R33") (pin "P$2") (pinfunction "2_P$2") (pintype "passive"))
    )
    (net (code "45") (name "Net-(IC4-ON1)") (class "Default")
      (node (ref "C7") (pin "2") (pinfunction "2_2") (pintype "passive"))
      (node (ref "IC4") (pin "1") (pinfunction "ON1_1") (pintype "passive"))
    )
    (net (code "46") (name "Net-(IC4-OPT)") (class "Default")
      (node (ref "C5") (pin "2") (pinfunction "2_2") (pintype "passive"))
      (node (ref "IC4") (pin "8") (pinfunction "OPT_8") (pintype "passive"))
    )
    (net (code "47") (name "Net-(IC5-+IN)") (class "Default")
      (node (ref "C8") (pin "2") (pinfunction "2_2") (pintype "passive"))
      (node (ref "IC5") (pin "3") (pinfunction "+IN_3") (pintype "input"))
      (node (ref "R34") (pin "P$2") (pinfunction "2_P$2") (pintype "passive"))
    )
    (net (code "48") (name "Net-(IC6-R)") (class "Default")
      (node (ref "IC6") (pin "1") (pinfunction "R_1") (pintype "bidirectional"))
      (node (ref "R43") (pin "P$2") (pinfunction "2_P$2") (pintype "passive"))
      (node (ref "R44") (pin "P$2") (pinfunction "2_P$2") (pintype "passive"))
    )
    (net (code "49") (name "Net-(IC7-D1)") (class "Default")
      (node (ref "IC7") (pin "2") (pinfunction "D1_2") (pintype "bidirectional"))
      (node (ref "IC7") (pin "6") (pinfunction "S4_6") (pintype "bidirectional"))
      (node (ref "IC8") (pin "2") (pinfunction "-IN_2") (pintype "input"))
    )
    (net (code "50") (name "Net-(IC7-D4)") (class "Default")
      (node (ref "IC7") (pin "11") (pinfunction "S3_11") (pintype "bidirectional"))
      (node (ref "IC7") (pin "7") (pinfunction "D4_7") (pintype "bidirectional"))
      (node (ref "RN2") (pin "10") (pinfunction "10A_10") (pintype "bidirectional"))
    )
    (net (code "51") (name "Net-(IC7-S1)") (class "Default")
      (node (ref "IC7") (pin "14") (pinfunction "S2_14") (pintype "bidirectional"))
      (node (ref "IC7") (pin "3") (pinfunction "S1_3") (pintype "bidirectional"))
      (node (ref "R45") (pin "P$1") (pinfunction "1_P$1") (pintype "passive"))
    )
    (net (code "52") (name "Net-(IC8A-OUT)") (class "Default")
      (node (ref "IC8") (pin "1") (pinfunction "OUT_1") (pintype "output"))
      (node (ref "T5") (pin "3") (pinfunction "G_3") (pintype "bidirectional"))
    )
    (net (code "53") (name "Net-(IC8B-+IN)") (class "Default")
      (node (ref "IC8") (pin "5") (pinfunction "+IN_5") (pintype "input"))
      (node (ref "RN2") (pin "7") (pinfunction "7A_7") (pintype "bidirectional"))
      (node (ref "T5") (pin "1") (pinfunction "D_1") (pintype "bidirectional"))
    )
    (net (code "54") (name "Net-(IC9-D2)") (class "Default")
      (node (ref "IC9") (pin "10") (pinfunction "D3_10") (pintype "bidirectional"))
      (node (ref "IC9") (pin "15") (pinfunction "D2_15") (pintype "bidirectional"))
      (node (ref "T6") (pin "1") (pinfunction "D_1") (pintype "bidirectional"))
    )
    (net (code "55") (name "Net-(IC9-S1)") (class "Default")
      (node (ref "IC9") (pin "14") (pinfunction "S2_14") (pintype "bidirectional"))
      (node (ref "IC9") (pin "3") (pinfunction "S1_3") (pintype "bidirectional"))
      (node (ref "RN2") (pin "15") (pinfunction "6B_15") (pintype "bidirectional"))
    )
    (net (code "56") (name "Net-(IC9-S3)") (class "Default")
      (node (ref "IC9") (pin "11") (pinfunction "S3_11") (pintype "bidirectional"))
      (node (ref "IC9") (pin "6") (pinfunction "S4_6") (pintype "bidirectional"))
      (node (ref "RN2") (pin "1") (pinfunction "1A_1") (pintype "bidirectional"))
      (node (ref "RN2") (pin "2") (pinfunction "2A_2") (pintype "bidirectional"))
      (node (ref "RN2") (pin "3") (pinfunction "3A_3") (pintype "bidirectional"))
      (node (ref "RN2") (pin "4") (pinfunction "4A_4") (pintype "bidirectional"))
    )
    (net (code "57") (name "Net-(IC10-+IN)") (class "Default")
      (node (ref "IC10") (pin "3") (pinfunction "+IN_3") (pintype "input"))
      (node (ref "RN1") (pin "4") (pinfunction "4A_4") (pintype "bidirectional"))
      (node (ref "RN1") (pin "5") (pinfunction "5A_5") (pintype "bidirectional"))
    )
    (net (code "58") (name "Net-(IC10--IN)") (class "Default")
      (node (ref "IC10") (pin "2") (pinfunction "-IN_2") (pintype "input"))
      (node (ref "RN1") (pin "2") (pinfunction "2A_2") (pintype "bidirectional"))
      (node (ref "RN1") (pin "7") (pinfunction "7A_7") (pintype "bidirectional"))
    )
    (net (code "59") (name "Net-(IC11-D+)") (class "Default")
      (node (ref "IC11") (pin "4") (pinfunction "D+_4") (pintype "bidirectional"))
      (node (ref "USB1") (pin "D+") (pinfunction "D+_D+") (pintype "bidirectional"))
    )
    (net (code "60") (name "Net-(IC11-D-)") (class "Default")
      (node (ref "IC11") (pin "5") (pinfunction "D-_5") (pintype "bidirectional"))
      (node (ref "USB1") (pin "D-") (pinfunction "D-_D-") (pintype "bidirectional"))
    )
    (net (code "61") (name "Net-(IC11-REGIN)") (class "Default")
      (node (ref "C16") (pin "2") (pinfunction "2_2") (pintype "passive"))
      (node (ref "IC11") (pin "7") (pinfunction "REGIN_7") (pintype "passive"))
      (node (ref "R53") (pin "P$1") (pinfunction "1_P$1") (pintype "passive"))
      (node (ref "USB1") (pin "VBUS") (pinfunction "VBUS_VBUS") (pintype "bidirectional"))
    )
    (net (code "62") (name "Net-(IC11-RXD)") (class "Default")
      (node (ref "IC11") (pin "25") (pinfunction "RXD_25") (pintype "input"))
      (node (ref "U1") (pin "6") (pinfunction "VOB_6") (pintype "output"))
    )
    (net (code "63") (name "Net-(IC11-TXD)") (class "Default")
      (node (ref "IC11") (pin "26") (pinfunction "TXD_26") (pintype "output"))
      (node (ref "U1") (pin "7") (pinfunction "VIA_7") (pintype "input"))
    )
    (net (code "64") (name "Net-(IC11-VBUS)") (class "Default")
      (node (ref "IC11") (pin "8") (pinfunction "VBUS_8") (pintype "input"))
      (node (ref "R52") (pin "P$1") (pinfunction "1_P$1") (pintype "passive"))
      (node (ref "R53") (pin "P$2") (pinfunction "2_P$2") (pintype "passive"))
    )
    (net (code "65") (name "Net-(IC11-VDD)") (class "Default")
      (node (ref "C14") (pin "2") (pinfunction "2_2") (pintype "passive"))
      (node (ref "C15") (pin "1") (pinfunction "1_1") (pintype "passive"))
      (node (ref "IC11") (pin "6") (pinfunction "VDD_6") (pintype "power_in"))
      (node (ref "U1") (pin "8") (pinfunction "VDD2_8") (pintype "power_in"))
    )
    (net (code "66") (name "Net-(IC12-D1)") (class "Default")
      (node (ref "IC12") (pin "2") (pinfunction "D1_2") (pintype "bidirectional"))
      (node (ref "R55") (pin "P$1") (pinfunction "1_P$1") (pintype "passive"))
    )
    (net (code "67") (name "Net-(IC12-D2)") (class "Default")
      (node (ref "IC12") (pin "15") (pinfunction "D2_15") (pintype "bidirectional"))
      (node (ref "R5") (pin "P$1") (pinfunction "1_P$1") (pintype "passive"))
    )
    (net (code "68") (name "Net-(IC12-D3)") (class "Default")
      (node (ref "IC12") (pin "10") (pinfunction "D3_10") (pintype "bidirectional"))
      (node (ref "R6") (pin "P$1") (pinfunction "1_P$1") (pintype "passive"))
    )
    (net (code "69") (name "Net-(IC12-D4)") (class "Default")
      (node (ref "IC12") (pin "7") (pinfunction "D4_7") (pintype "bidirectional"))
      (node (ref "IC3") (pin "10") (pinfunction "D3_10") (pintype "bidirectional"))
      (node (ref "IC3") (pin "7") (pinfunction "D4_7") (pintype "bidirectional"))
    )
    (net (code "70") (name "Net-(IC12-S1)") (class "Default")
      (node (ref "IC12") (pin "11") (pinfunction "S3_11") (pintype "bidirectional"))
      (node (ref "IC12") (pin "14") (pinfunction "S2_14") (pintype "bidirectional"))
      (node (ref "IC12") (pin "3") (pinfunction "S1_3") (pintype "bidirectional"))
      (node (ref "IC12") (pin "6") (pinfunction "S4_6") (pintype "bidirectional"))
      (node (ref "R33") (pin "P$1") (pinfunction "1_P$1") (pintype "passive"))
    )
    (net (code "71") (name "Net-(IC13-A)") (class "Default")
      (node (ref "IC13") (pin "3") (pinfunction "A_3") (pintype "bidirectional"))
      (node (ref "IC14") (pin "2") (pinfunction "C_2") (pintype "bidirectional"))
      (node (ref "IC5") (pin "2") (pinfunction "-IN_2") (pintype "input"))
      (node (ref "IC5") (pin "6") (pinfunction "OUT_6") (pintype "output"))
      (node (ref "R39") (pin "P$1") (pinfunction "1_P$1") (pintype "passive"))
      (node (ref "R40") (pin "P$1") (pinfunction "1_P$1") (pintype "passive"))
    )
    (net (code "72") (name "Net-(IC13-C)") (class "Default")
      (node (ref "IC13") (pin "2") (pinfunction "C_2") (pintype "bidirectional"))
      (node (ref "R35") (pin "P$1") (pinfunction "1_P$1") (pintype "passive"))
      (node (ref "R37") (pin "P$1") (pinfunction "1_P$1") (pintype "passive"))
      (node (ref "T3") (pin "1") (pinfunction "B_1") (pintype "passive"))
    )
    (net (code "73") (name "Net-(IC13-R)") (class "Default")
      (node (ref "IC13") (pin "1") (pinfunction "R_1") (pintype "bidirectional"))
      (node (ref "R37") (pin "P$2") (pinfunction "2_P$2") (pintype "passive"))
      (node (ref "R39") (pin "P$2") (pinfunction "2_P$2") (pintype "passive"))
    )
    (net (code "74") (name "Net-(IC14-A)") (class "Default")
      (node (ref "IC14") (pin "3") (pinfunction "A_3") (pintype "bidirectional"))
      (node (ref "R36") (pin "P$2") (pinfunction "2_P$2") (pintype "passive"))
      (node (ref "R38") (pin "P$1") (pinfunction "1_P$1") (pintype "passive"))
      (node (ref "T4") (pin "1") (pinfunction "B_1") (pintype "passive"))
    )
    (net (code "75") (name "Net-(IC14-R)") (class "Default")
      (node (ref "IC14") (pin "1") (pinfunction "R_1") (pintype "bidirectional"))
      (node (ref "R38") (pin "P$2") (pinfunction "2_P$2") (pintype "passive"))
      (node (ref "R40") (pin "P$2") (pinfunction "2_P$2") (pintype "passive"))
    )
    (net (code "76") (name "Net-(IC15-+IN)") (class "Default")
      (node (ref "IC15") (pin "3") (pinfunction "+IN_3") (pintype "input"))
      (node (ref "IC4") (pin "6") (pinfunction "OUT_6") (pintype "output"))
    )
    (net (code "77") (name "Net-(IC15--IN)") (class "Default")
      (node (ref "IC15") (pin "2") (pinfunction "-IN_2") (pintype "input"))
      (node (ref "IC3") (pin "14") (pinfunction "S2_14") (pintype "bidirectional"))
      (node (ref "IC3") (pin "3") (pinfunction "S1_3") (pintype "bidirectional"))
      (node (ref "IC4") (pin "2") (pinfunction "-IN_2") (pintype "input"))
      (node (ref "R34") (pin "P$1") (pinfunction "1_P$1") (pintype "passive"))
    )
    (net (code "78") (name "Net-(K1B-S)") (class "Default")
      (node (ref "K1") (pin "1") (pinfunction "S_1") (pintype "passive"))
      (node (ref "K4") (pin "1") (pinfunction "S_1") (pintype "passive"))
      (node (ref "R19") (pin "P$1") (pinfunction "1_P$1") (pintype "passive"))
      (node (ref "U$2") (pin "2") (pinfunction "P$2_2") (pintype "bidirectional"))
    )
    (net (code "79") (name "Net-(K2B-S)") (class "Default")
      (node (ref "K2") (pin "1") (pinfunction "S_1") (pintype "passive"))
      (node (ref "R3") (pin "P$2") (pinfunction "2_P$2") (pintype "passive"))
    )
    (net (code "80") (name "Net-(K3B-S)") (class "Default")
      (node (ref "K3") (pin "1") (pinfunction "S_1") (pintype "passive"))
      (node (ref "R8") (pin "P$1") (pinfunction "1_P$1") (pintype "passive"))
      (node (ref "U$1") (pin "2") (pinfunction "P$2_2") (pintype "bidirectional"))
    )
    (net (code "81") (name "Net-(K4B-P)") (class "Default")
      (node (ref "K4") (pin "4") (pinfunction "P_4") (pintype "passive"))
      (node (ref "R17") (pin "P$1") (pinfunction "1_P$1") (pintype "passive"))
      (node (ref "R18") (pin "P$1") (pinfunction "1_P$1") (pintype "passive"))
    )
    (net (code "82") (name "Net-(R1-1)") (class "Default")
      (node (ref "C1") (pin "2") (pinfunction "2_2") (pintype "passive"))
      (node (ref "R1") (pin "P$1") (pinfunction "1_P$1") (pintype "passive"))
      (node (ref "R5") (pin "P$2") (pinfunction "2_P$2") (pintype "passive"))
    )
    (net (code "83") (name "Net-(R2-1)") (class "Default")
      (node (ref "C2") (pin "2") (pinfunction "2_2") (pintype "passive"))
      (node (ref "R2") (pin "P$1") (pinfunction "1_P$1") (pintype "passive"))
      (node (ref "R6") (pin "P$2") (pinfunction "2_P$2") (pintype "passive"))
    )
    (net (code "84") (name "Net-(R3-1)") (class "Default")
      (node (ref "R3") (pin "P$1") (pinfunction "1_P$1") (pintype "passive"))
      (node (ref "R4") (pin "P$1") (pinfunction "1_P$1") (pintype "passive"))
    )
    (net (code "85") (name "Net-(R4-2)") (class "Default")
      (node (ref "R4") (pin "P$2") (pinfunction "2_P$2") (pintype "passive"))
      (node (ref "R9") (pin "P$2") (pinfunction "2_P$2") (pintype "passive"))
    )
    (net (code "86") (name "Net-(R7-1)") (class "Default")
      (node (ref "R7") (pin "P$1") (pinfunction "1_P$1") (pintype "passive"))
      (node (ref "T1") (pin "1") (pinfunction "B_1") (pintype "passive"))
    )
    (net (code "87") (name "Net-(R10-1)") (class "Default")
      (node (ref "R10") (pin "P$1") (pinfunction "1_P$1") (pintype "passive"))
      (node (ref "R9") (pin "P$1") (pinfunction "1_P$1") (pintype "passive"))
    )
    (net (code "88") (name "Net-(R10-2)") (class "Default")
      (node (ref "R10") (pin "P$2") (pinfunction "2_P$2") (pintype "passive"))
      (node (ref "R11") (pin "P$2") (pinfunction "2_P$2") (pintype "passive"))
    )
    (net (code "89") (name "Net-(R11-1)") (class "Default")
      (node (ref "R11") (pin "P$1") (pinfunction "1_P$1") (pintype "passive"))
      (node (ref "R12") (pin "P$1") (pinfunction "1_P$1") (pintype "passive"))
    )
    (net (code "90") (name "Net-(R12-2)") (class "Default")
      (node (ref "R12") (pin "P$2") (pinfunction "2_P$2") (pintype "passive"))
      (node (ref "R14") (pin "P$2") (pinfunction "2_P$2") (pintype "passive"))
    )
    (net (code "91") (name "Net-(R13-1)") (class "Default")
      (node (ref "JP1") (pin "7") (pinfunction "7_7") (pintype "passive"))
      (node (ref "R13") (pin "P$1") (pinfunction "1_P$1") (pintype "passive"))
      (node (ref "T2") (pin "2") (pinfunction "C_2") (pintype "passive"))
    )
    (net (code "92") (name "Net-(R13-2)") (class "Default")
      (node (ref "D3") (pin "A") (pinfunction "A_A") (pintype "input"))
      (node (ref "R13") (pin "P$2") (pinfunction "2_P$2") (pintype "passive"))
      (node (ref "T2") (pin "1") (pinfunction "B_1") (pintype "passive"))
    )
    (net (code "93") (name "Net-(R14-1)") (class "Default")
      (node (ref "R14") (pin "P$1") (pinfunction "1_P$1") (pintype "passive"))
      (node (ref "R16") (pin "P$1") (pinfunction "1_P$1") (pintype "passive"))
    )
    (net (code "94") (name "Net-(R15-1)") (class "Default")
      (node (ref "R15") (pin "P$1") (pinfunction "1_P$1") (pintype "passive"))
      (node (ref "R62") (pin "P$1") (pinfunction "1_P$1") (pintype "passive"))
      (node (ref "T1") (pin "3") (pinfunction "C_3") (pintype "passive"))
    )
    (net (code "95") (name "Net-(R15-2)") (class "Default")
      (node (ref "D3") (pin "K") (pinfunction "K_K") (pintype "output"))
      (node (ref "R15") (pin "P$2") (pinfunction "2_P$2") (pintype "passive"))
    )
    (net (code "96") (name "Net-(R16-2)") (class "Default")
      (node (ref "R16") (pin "P$2") (pinfunction "2_P$2") (pintype "passive"))
      (node (ref "R18") (pin "P$2") (pinfunction "2_P$2") (pintype "passive"))
    )
    (net (code "97") (name "Net-(R19-2)") (class "Default")
      (node (ref "R19") (pin "P$2") (pinfunction "2_P$2") (pintype "passive"))
      (node (ref "R20") (pin "P$2") (pinfunction "2_P$2") (pintype "passive"))
      (node (ref "U$2") (pin "1") (pinfunction "P$1_1") (pintype "bidirectional"))
    )
    (net (code "98") (name "Net-(R20-1)") (class "Default")
      (node (ref "C3") (pin "2") (pinfunction "2_2") (pintype "passive"))
      (node (ref "R20") (pin "P$1") (pinfunction "1_P$1") (pintype "passive"))
      (node (ref "R55") (pin "P$2") (pinfunction "2_P$2") (pintype "passive"))
    )
    (net (code "99") (name "Net-(R45-2)") (class "Default")
      (node (ref "R45") (pin "P$2") (pinfunction "2_P$2") (pintype "passive"))
      (node (ref "R46") (pin "P$1") (pinfunction "1_P$1") (pintype "passive"))
    )
    (net (code "100") (name "Net-(R46-2)") (class "Default")
      (node (ref "R46") (pin "P$2") (pinfunction "2_P$2") (pintype "passive"))
      (node (ref "RN2") (pin "9") (pinfunction "9A_9") (pintype "bidirectional"))
      (node (ref "T5") (pin "2") (pinfunction "S_2") (pintype "bidirectional"))
    )
    (net (code "101") (name "Net-(R47-2)") (class "Default")
      (node (ref "D1") (pin "C") (pinfunction "C_C") (pintype "passive"))
      (node (ref "R47") (pin "P$2") (pinfunction "2_P$2") (pintype "passive"))
      (node (ref "T6") (pin "3") (pinfunction "G_3") (pintype "bidirectional"))
    )
    (net (code "102") (name "Net-(R48-2)") (class "Default")
      (node (ref "D5") (pin "A") (pinfunction "A_A") (pintype "passive"))
      (node (ref "R48") (pin "P$2") (pinfunction "2_P$2") (pintype "passive"))
      (node (ref "RN2") (pin "14") (pinfunction "7B_14") (pintype "bidirectional"))
      (node (ref "RN2") (pin "18") (pinfunction "3B_18") (pintype "bidirectional"))
      (node (ref "RN2") (pin "19") (pinfunction "2B_19") (pintype "bidirectional"))
      (node (ref "RN2") (pin "20") (pinfunction "1B_20") (pintype "bidirectional"))
      (node (ref "T13") (pin "3") (pinfunction "E_3") (pintype "passive"))
    )
    (net (code "103") (name "Net-(R49-2)") (class "Default")
      (node (ref "R49") (pin "P$2") (pinfunction "2_P$2") (pintype "passive"))
      (node (ref "T7") (pin "1") (pinfunction "D_1") (pintype "bidirectional"))
      (node (ref "T7") (pin "2") (pinfunction "S_2") (pintype "bidirectional"))
      (node (ref "T9") (pin "1") (pinfunction "B_1") (pintype "passive"))
    )
    (net (code "104") (name "Net-(R50-1)") (class "Default")
      (node (ref "P2") (pin "TP") (pinfunction "TP_TP") (pintype "input"))
      (node (ref "R50") (pin "P$1") (pinfunction "1_P$1") (pintype "passive"))
      (node (ref "U$7") (pin "2") (pinfunction "P$2_2") (pintype "bidirectional"))
      (node (ref "X3") (pin "2") (pinfunction "2_2") (pintype "passive"))
    )
    (net (code "105") (name "Net-(R51-1)") (class "Default")
      (node (ref "P3") (pin "TP") (pinfunction "TP_TP") (pintype "input"))
      (node (ref "R51") (pin "P$1") (pinfunction "1_P$1") (pintype "passive"))
      (node (ref "U$8") (pin "2") (pinfunction "P$2_2") (pintype "bidirectional"))
      (node (ref "X4") (pin "2") (pinfunction "2_2") (pintype "passive"))
    )
    (net (code "106") (name "Net-(R54-1)") (class "Default")
      (node (ref "C17") (pin "2") (pinfunction "2_2") (pintype "passive"))
      (node (ref "R54") (pin "P$1") (pinfunction "1_P$1") (pintype "passive"))
      (node (ref "USB1") (pin "GND@1") (pinfunction "GND_GND@1") (pintype "bidirectional"))
      (node (ref "USB1") (pin "GND@2") (pinfunction "GND_GND@2") (pintype "bidirectional"))
    )
    (net (code "107") (name "Net-(R59-1)") (class "Default")
      (node (ref "R59") (pin "P$1") (pinfunction "1_P$1") (pintype "passive"))
      (node (ref "R60") (pin "P$2") (pinfunction "2_P$2") (pintype "passive"))
    )
    (net (code "108") (name "Net-(R59-2)") (class "Default")
      (node (ref "R58") (pin "2") (pinfunction "2_2") (pintype "passive"))
      (node (ref "R59") (pin "P$2") (pinfunction "2_P$2") (pintype "passive"))
      (node (ref "X2") (pin "1") (pinfunction "1_1") (pintype "passive"))
    )
    (net (code "109") (name "Net-(R61-2)") (class "Default")
      (node (ref "D4") (pin "A") (pinfunction "A_A") (pintype "input"))
      (node (ref "R61") (pin "P$2") (pinfunction "2_P$2") (pintype "passive"))
      (node (ref "T10") (pin "1") (pinfunction "B_1") (pintype "passive"))
    )
    (net (code "110") (name "Net-(R62-2)") (class "Default")
      (node (ref "D4") (pin "K") (pinfunction "K_K") (pintype "output"))
      (node (ref "R62") (pin "P$2") (pinfunction "2_P$2") (pintype "passive"))
    )
    (net (code "111") (name "Net-(R67-1)") (class "Default")
      (node (ref "R67") (pin "P$1") (pinfunction "1_P$1") (pintype "passive"))
      (node (ref "R68") (pin "P$1") (pinfunction "1_P$1") (pintype "passive"))
      (node (ref "T13") (pin "1") (pinfunction "B_1") (pintype "passive"))
    )
    (net (code "112") (name "Net-(R68-2)") (class "Default")
      (node (ref "R68") (pin "P$2") (pinfunction "2_P$2") (pintype "passive"))
      (node (ref "T14") (pin "3") (pinfunction "C_3") (pintype "passive"))
    )
    (net (code "113") (name "Net-(R69-2)") (class "Default")
      (node (ref "R69") (pin "P$2") (pinfunction "2_P$2") (pintype "passive"))
      (node (ref "T14") (pin "1") (pinfunction "B_1") (pintype "passive"))
    )
    (net (code "114") (name "Net-(RN1-1B)") (class "Default")
      (node (ref "RN1") (pin "19") (pinfunction "2B_19") (pintype "bidirectional"))
      (node (ref "RN1") (pin "20") (pinfunction "1B_20") (pintype "bidirectional"))
    )
    (net (code "115") (name "Net-(RN1-3B)") (class "Default")
      (node (ref "RN1") (pin "17") (pinfunction "4B_17") (pintype "bidirectional"))
      (node (ref "RN1") (pin "18") (pinfunction "3B_18") (pintype "bidirectional"))
    )
    (net (code "116") (name "Net-(RN1-5B)") (class "Default")
      (node (ref "RN1") (pin "15") (pinfunction "6B_15") (pintype "bidirectional"))
      (node (ref "RN1") (pin "16") (pinfunction "5B_16") (pintype "bidirectional"))
    )
    (net (code "117") (name "Net-(RN1-7B)") (class "Default")
      (node (ref "RN1") (pin "13") (pinfunction "8B_13") (pintype "bidirectional"))
      (node (ref "RN1") (pin "14") (pinfunction "7B_14") (pintype "bidirectional"))
    )
    (net (code "118") (name "Net-(RN2-4B)") (class "Default")
      (node (ref "RN2") (pin "16") (pinfunction "5B_16") (pintype "bidirectional"))
      (node (ref "RN2") (pin "17") (pinfunction "4B_17") (pintype "bidirectional"))
    )
    (net (code "119") (name "Net-(RN2-5A)") (class "Default")
      (node (ref "RN2") (pin "5") (pinfunction "5A_5") (pintype "bidirectional"))
      (node (ref "RN2") (pin "6") (pinfunction "6A_6") (pintype "bidirectional"))
    )
    (net (code "120") (name "Net-(RN2-10B)") (class "Default")
      (node (ref "RN2") (pin "11") (pinfunction "10B_11") (pintype "bidirectional"))
      (node (ref "RN2") (pin "12") (pinfunction "9B_12") (pintype "bidirectional"))
    )
    (net (code "121") (name "Net-(RN3-R1B)") (class "Default")
      (node (ref "RN3") (pin "5") (pinfunction "R4B_5") (pintype "bidirectional"))
      (node (ref "RN3") (pin "8") (pinfunction "R1B_8") (pintype "bidirectional"))
    )
    (net (code "122") (name "Net-(RN3-R2B)") (class "Default")
      (node (ref "RN3") (pin "6") (pinfunction "R3B_6") (pintype "bidirectional"))
      (node (ref "RN3") (pin "7") (pinfunction "R2B_7") (pintype "bidirectional"))
    )
    (net (code "123") (name "Net-(T2-E)") (class "Default")
      (node (ref "C4") (pin "2") (pinfunction "2_2") (pintype "passive"))
      (node (ref "T2") (pin "3") (pinfunction "E_3") (pintype "passive"))
      (node (ref "U1") (pin "1") (pinfunction "VDD1_1") (pintype "power_in"))
    )
    (net (code "124") (name "Net-(T6-S)") (class "Default")
      (node (ref "T6") (pin "2") (pinfunction "S_2") (pintype "bidirectional"))
      (node (ref "T9") (pin "2") (pinfunction "C_2") (pintype "passive"))
    )
    (net (code "125") (name "Net-(T9-E)") (class "Default")
      (node (ref "D2") (pin "A") (pinfunction "A_A") (pintype "input"))
      (node (ref "T9") (pin "3") (pinfunction "E_3") (pintype "passive"))
    )
    (net (code "126") (name "Net-(U1-VIB)") (class "Default")
      (node (ref "JP1") (pin "1") (pinfunction "1_1") (pintype "passive"))
      (node (ref "U1") (pin "3") (pinfunction "VIB_3") (pintype "input"))
    )
    (net (code "127") (name "Net-(U1-VOA)") (class "Default")
      (node (ref "JP1") (pin "2") (pinfunction "2_2") (pintype "passive"))
      (node (ref "U1") (pin "2") (pinfunction "VOA_2") (pintype "output"))
    )
    (net (code "128") (name "OHM_CUR") (class "Default")
      (node (ref "D2") (pin "K") (pinfunction "K_K") (pintype "output"))
      (node (ref "R49") (pin "P$1") (pinfunction "1_P$1") (pintype "passive"))
      (node (ref "R8") (pin "P$2") (pinfunction "2_P$2") (pintype "passive"))
      (node (ref "U$1") (pin "1") (pinfunction "P$1_1") (pintype "bidirectional"))
    )
    (net (code "129") (name "SR_CLK") (class "Default")
      (node (ref "IC1") (pin "11") (pinfunction "SCK_11") (pintype "input"))
      (node (ref "IC2") (pin "11") (pinfunction "SCK_11") (pintype "input"))
      (node (ref "JP1") (pin "3") (pinfunction "3_3") (pintype "passive"))
    )
    (net (code "130") (name "SR_DAT") (class "Default")
      (node (ref "IC1") (pin "14") (pinfunction "SER_14") (pintype "input"))
      (node (ref "JP1") (pin "4") (pinfunction "4_4") (pintype "passive"))
    )
    (net (code "131") (name "SR_LAT") (class "Default")
      (node (ref "IC1") (pin "12") (pinfunction "RCK_12") (pintype "input"))
      (node (ref "IC2") (pin "12") (pinfunction "RCK_12") (pintype "input"))
      (node (ref "JP1") (pin "5") (pinfunction "5_5") (pintype "passive"))
    )
    (net (code "132") (name "T_INP") (class "Default")
      (node (ref "K1") (pin "4") (pinfunction "P_4") (pintype "passive"))
      (node (ref "K2") (pin "4") (pinfunction "P_4") (pintype "passive"))
      (node (ref "K3") (pin "4") (pinfunction "P_4") (pintype "passive"))
      (node (ref "P1") (pin "TP") (pinfunction "TP_TP") (pintype "input"))
      (node (ref "X2") (pin "2") (pinfunction "2_2") (pintype "passive"))
    )
    (net (code "133") (name "T_SENH") (class "Default")
      (node (ref "R1") (pin "P$2") (pinfunction "2_P$2") (pintype "passive"))
      (node (ref "R50") (pin "P$2") (pinfunction "2_P$2") (pintype "passive"))
      (node (ref "U$7") (pin "1") (pinfunction "P$1_1") (pintype "bidirectional"))
    )
    (net (code "134") (name "T_SENL") (class "Default")
      (node (ref "R2") (pin "P$2") (pinfunction "2_P$2") (pintype "passive"))
      (node (ref "R51") (pin "P$2") (pinfunction "2_P$2") (pintype "passive"))
      (node (ref "U$8") (pin "1") (pinfunction "P$1_1") (pintype "bidirectional"))
    )
    (net (code "135") (name "V+") (class "Default")
      (node (ref "C9") (pin "1") (pinfunction "1_1") (pintype "passive"))
      (node (ref "IC4") (pin "7") (pinfunction "V+_7") (pintype "power_in"))
      (node (ref "IC5") (pin "7") (pinfunction "V+_7") (pintype "power_in"))
      (node (ref "T3") (pin "2") (pinfunction "E_2") (pintype "passive"))
    )
    (net (code "136") (name "V-") (class "Default")
      (node (ref "C10") (pin "2") (pinfunction "2_2") (pintype "passive"))
      (node (ref "C5") (pin "1") (pinfunction "1_1") (pintype "passive"))
      (node (ref "C7") (pin "1") (pinfunction "1_1") (pintype "passive"))
      (node (ref "C9") (pin "2") (pinfunction "2_2") (pintype "passive"))
      (node (ref "IC4") (pin "4") (pinfunction "V-_4") (pintype "power_in"))
      (node (ref "IC5") (pin "4") (pinfunction "V-_4") (pintype "power_in"))
      (node (ref "T4") (pin "2") (pinfunction "C_2") (pintype "passive"))
    )
    (net (code "137") (name "VCC") (class "Default")
      (node (ref "IC12") (pin "12") (pinfunction "VL_12") (pintype "bidirectional"))
      (node (ref "IC3") (pin "12") (pinfunction "VL_12") (pintype "bidirectional"))
      (node (ref "IC6") (pin "2") (pinfunction "C_2") (pintype "bidirectional"))
      (node (ref "IC7") (pin "12") (pinfunction "VL_12") (pintype "bidirectional"))
      (node (ref "IC9") (pin "12") (pinfunction "VL_12") (pintype "bidirectional"))
      (node (ref "R42") (pin "P$1") (pinfunction "1_P$1") (pintype "passive"))
      (node (ref "R43") (pin "P$1") (pinfunction "1_P$1") (pintype "passive"))
    )
    (net (code "138") (name "VREF-7V") (class "Default")
      (node (ref "IC7") (pin "10") (pinfunction "D3_10") (pintype "bidirectional"))
      (node (ref "IC7") (pin "15") (pinfunction "D2_15") (pintype "bidirectional"))
      (node (ref "JP3") (pin "1") (pinfunction "1_1") (pintype "passive"))
      (node (ref "R41") (pin "P$2") (pinfunction "2_P$2") (pintype "passive"))
    )
    (net (code "139") (name "V_REL") (class "Default")
      (node (ref "K1") (pin "2") (pinfunction "+_2") (pintype "passive"))
      (node (ref "K2") (pin "2") (pinfunction "+_2") (pintype "passive"))
      (node (ref "K3") (pin "2") (pinfunction "+_2") (pintype "passive"))
      (node (ref "K4") (pin "2") (pinfunction "+_2") (pintype "passive"))
      (node (ref "T10") (pin "3") (pinfunction "E_3") (pintype "passive"))
    )
    (net (code "140") (name "unconnected-(IC2A-QH*-Pad9)") (class "Default")
      (node (ref "IC2") (pin "9") (pinfunction "QH*_9") (pintype "tri_state"))
    )
    (net (code "141") (name "unconnected-(IC4-ON2-Pad5)") (class "Default")
      (node (ref "IC4") (pin "5") (pinfunction "ON2_5") (pintype "passive"))
    )
    (net (code "142") (name "unconnected-(IC5-ON1-Pad1)") (class "Default")
      (node (ref "IC5") (pin "1") (pinfunction "ON1_1") (pintype "passive"))
    )
    (net (code "143") (name "unconnected-(IC5-ON2-Pad5)") (class "Default")
      (node (ref "IC5") (pin "5") (pinfunction "ON2_5") (pintype "passive"))
    )
    (net (code "144") (name "unconnected-(IC5-OPT-Pad8)") (class "Default")
      (node (ref "IC5") (pin "8") (pinfunction "OPT_8") (pintype "passive"))
    )
    (net (code "145") (name "unconnected-(IC10-ON1-Pad1)") (class "Default")
      (node (ref "IC10") (pin "1") (pinfunction "ON1_1") (pintype "passive"))
    )
    (net (code "146") (name "unconnected-(IC10-ON2-Pad5)") (class "Default")
      (node (ref "IC10") (pin "5") (pinfunction "ON2_5") (pintype "passive"))
    )
    (net (code "147") (name "unconnected-(IC10-OPT-Pad8)") (class "Default")
      (node (ref "IC10") (pin "8") (pinfunction "OPT_8") (pintype "passive"))
    )
    (net (code "148") (name "unconnected-(IC11-CTS-Pad23)") (class "Default")
      (node (ref "IC11") (pin "23") (pinfunction "CTS_23") (pintype "input"))
    )
    (net (code "149") (name "unconnected-(IC11-DCD-Pad1)") (class "Default")
      (node (ref "IC11") (pin "1") (pinfunction "DCD_1") (pintype "input"))
    )
    (net (code "150") (name "unconnected-(IC11-DSR-Pad27)") (class "Default")
      (node (ref "IC11") (pin "27") (pinfunction "DSR_27") (pintype "input"))
    )
    (net (code "151") (name "unconnected-(IC11-DTR-Pad28)") (class "Default")
      (node (ref "IC11") (pin "28") (pinfunction "DTR_28") (pintype "output"))
    )
    (net (code "152") (name "unconnected-(IC11-RI-Pad2)") (class "Default")
      (node (ref "IC11") (pin "2") (pinfunction "RI_2") (pintype "input"))
    )
    (net (code "153") (name "unconnected-(IC11-RTS-Pad24)") (class "Default")
      (node (ref "IC11") (pin "24") (pinfunction "RTS_24") (pintype "output"))
    )
    (net (code "154") (name "unconnected-(IC11-SUSPEND-Pad12)") (class "Default")
      (node (ref "IC11") (pin "12") (pinfunction "SUSPEND_12") (pintype "output"))
    )
    (net (code "155") (name "unconnected-(IC11-~{RST}-Pad9)") (class "Default")
      (node (ref "IC11") (pin "9") (pinfunction "~{RST}_9") (pintype "bidirectional"))
    )
    (net (code "156") (name "unconnected-(IC11-~{SUSPEND}-Pad11)") (class "Default")
      (node (ref "IC11") (pin "11") (pinfunction "~{SUSPEND}_11") (pintype "output"))
    )
    (net (code "157") (name "unconnected-(IC15-ON1-Pad1)") (class "Default")
      (node (ref "IC15") (pin "1") (pinfunction "ON1_1") (pintype "passive"))
    )
    (net (code "158") (name "unconnected-(IC15-ON2-Pad5)") (class "Default")
      (node (ref "IC15") (pin "5") (pinfunction "ON2_5") (pintype "passive"))
    )
    (net (code "159") (name "unconnected-(IC15-OPT-Pad8)") (class "Default")
      (node (ref "IC15") (pin "8") (pinfunction "OPT_8") (pintype "passive"))
    )
    (net (code "160") (name "unconnected-(RN1-9A-Pad9)") (class "Default")
      (node (ref "RN1") (pin "9") (pinfunction "9A_9") (pintype "bidirectional"))
    )
    (net (code "161") (name "unconnected-(RN1-9B-Pad12)") (class "Default")
      (node (ref "RN1") (pin "12") (pinfunction "9B_12") (pintype "bidirectional"))
    )
    (net (code "162") (name "unconnected-(RN1-10A-Pad10)") (class "Default")
      (node (ref "RN1") (pin "10") (pinfunction "10A_10") (pintype "bidirectional"))
    )
    (net (code "163") (name "unconnected-(RN1-10B-Pad11)") (class "Default")
      (node (ref "RN1") (pin "11") (pinfunction "10B_11") (pintype "bidirectional"))
    )
    (net (code "164") (name "unconnected-(RN2-8A-Pad8)") (class "Default")
      (node (ref "RN2") (pin "8") (pinfunction "8A_8") (pintype "bidirectional"))
    )
    (net (code "165") (name "unconnected-(RN2-8B-Pad13)") (class "Default")
      (node (ref "RN2") (pin "13") (pinfunction "8B_13") (pintype "bidirectional"))
    )
  )
)
